# MAX96724_PINOUT.net
KiCad netlist of a schematic drawn in Altium Designer
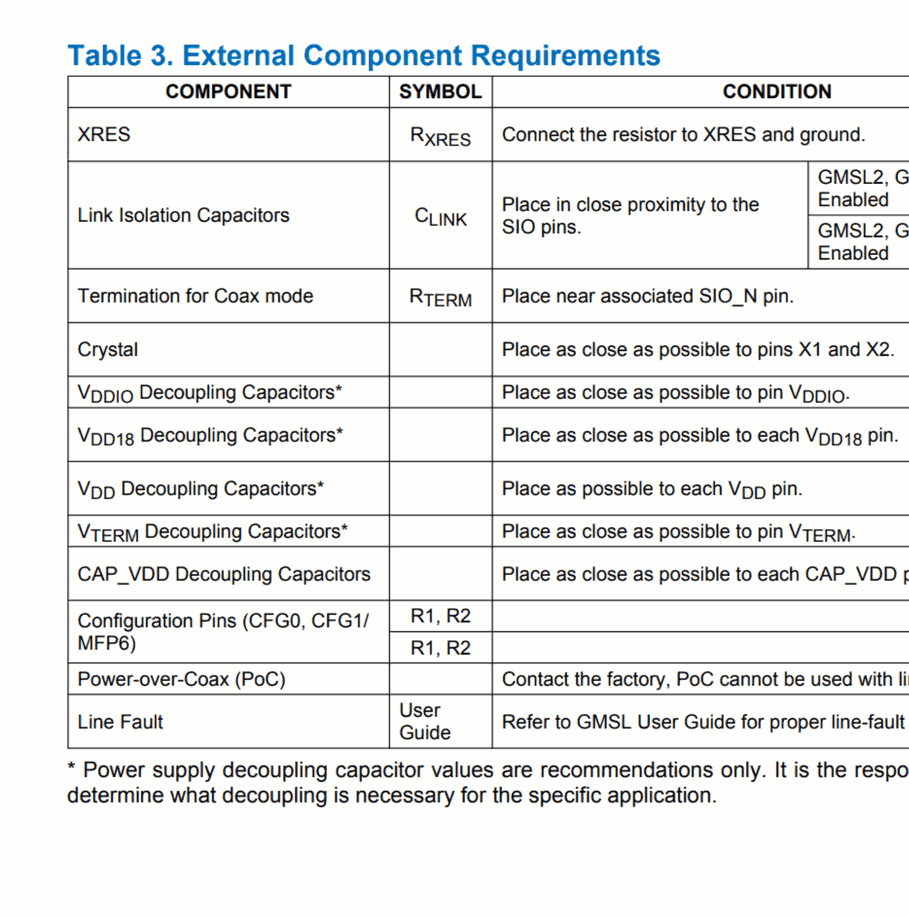
[diagram p0: MAX96724_PINOUT.SchDoc, top left]
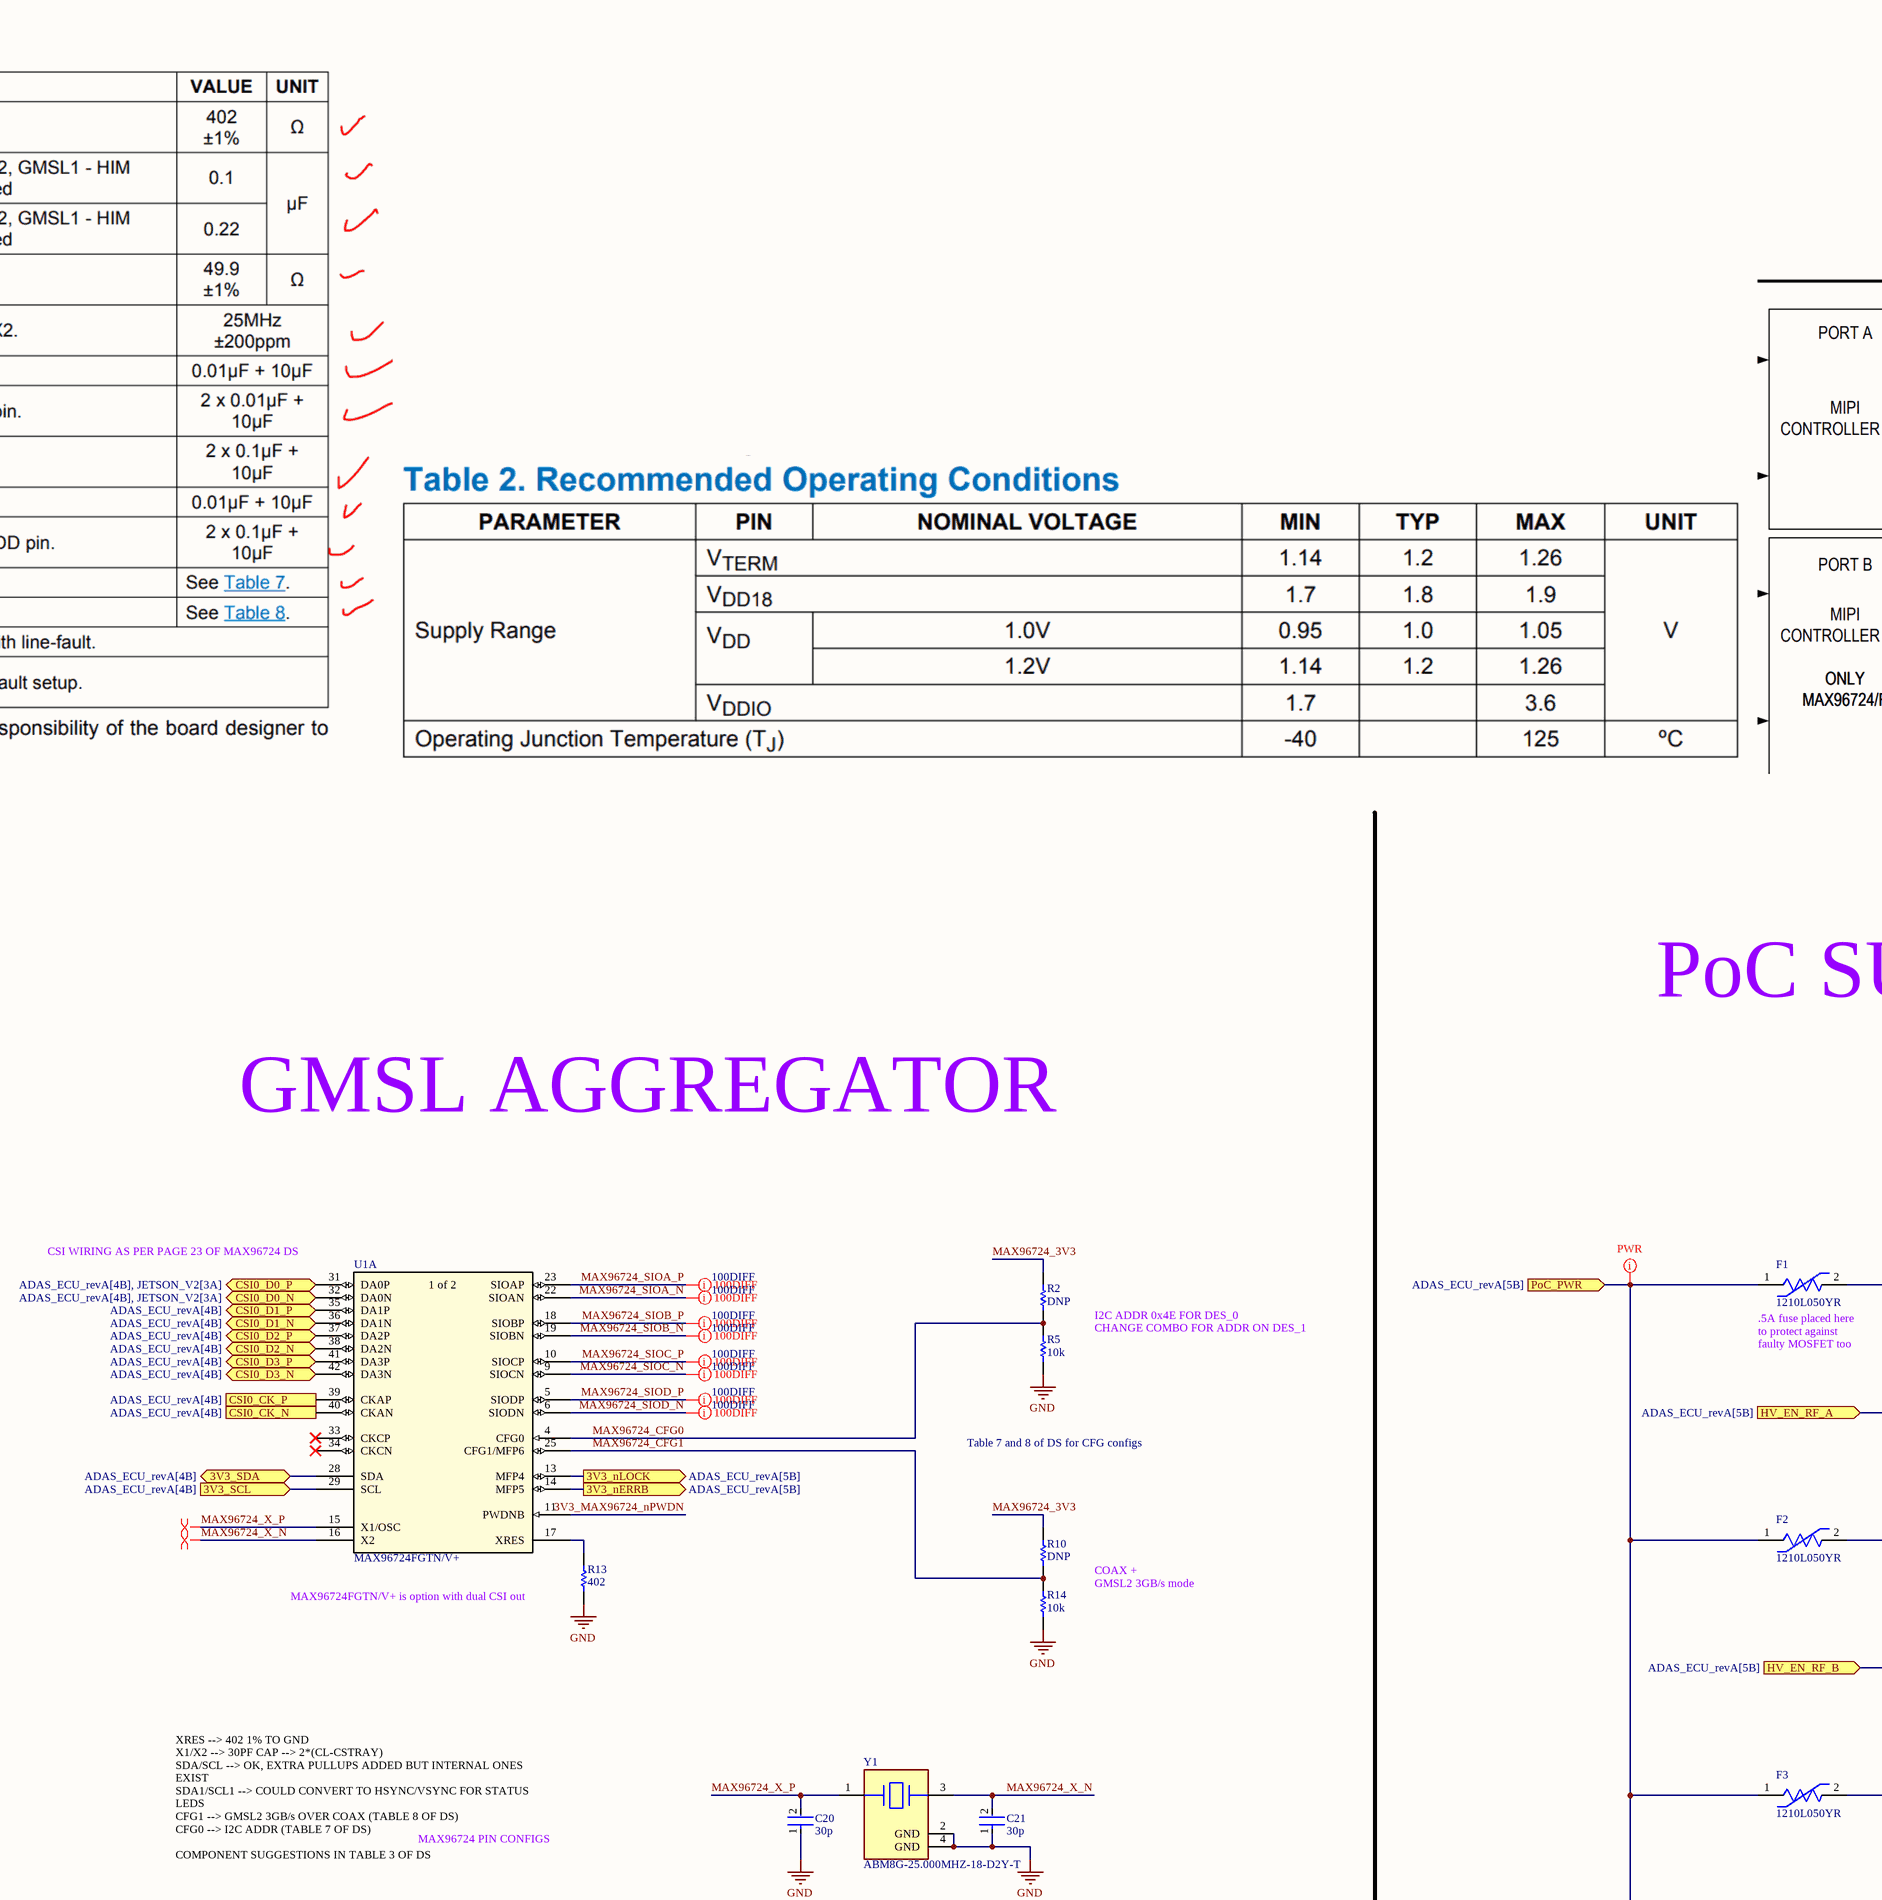
[diagram p1: MAX96724_PINOUT.SchDoc, top middle]
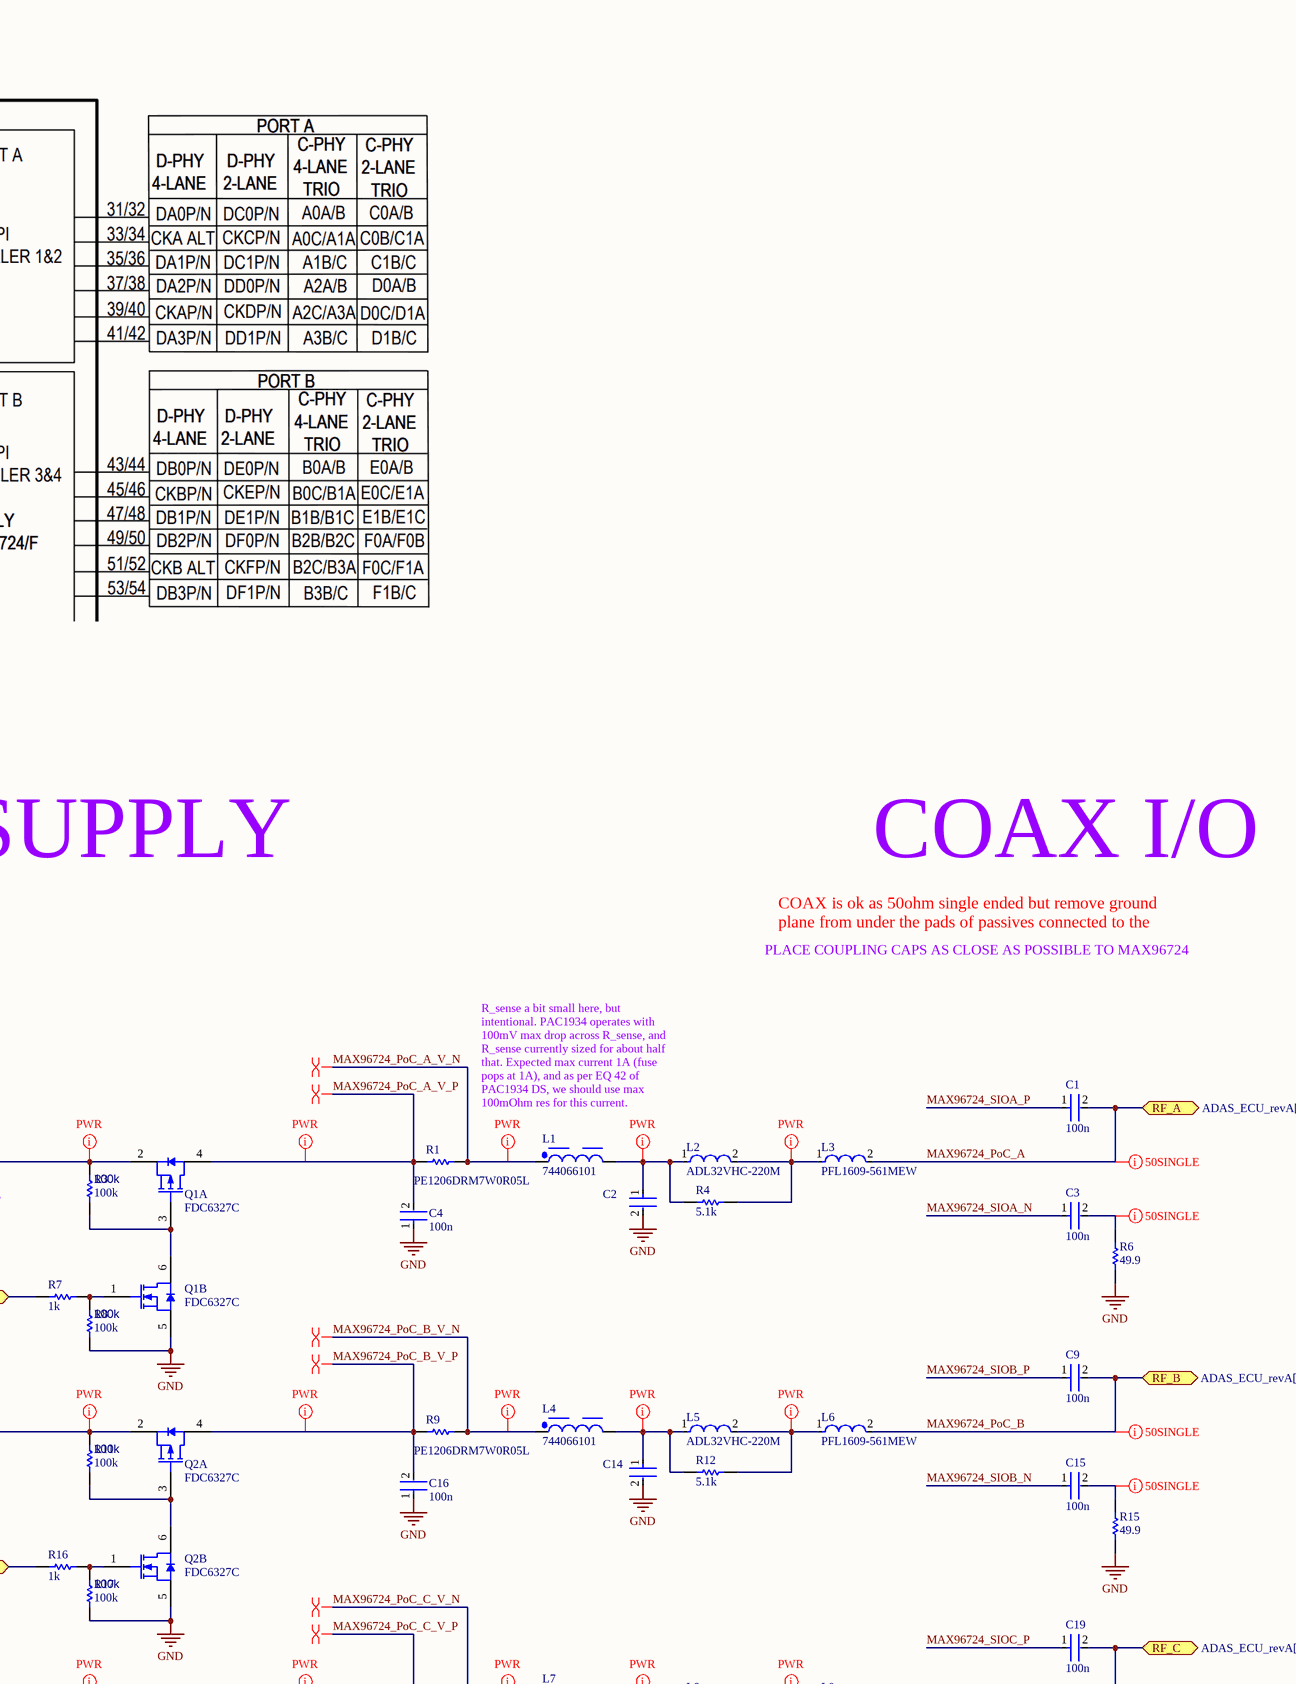
[diagram p2: MAX96724_PINOUT.SchDoc, top right]
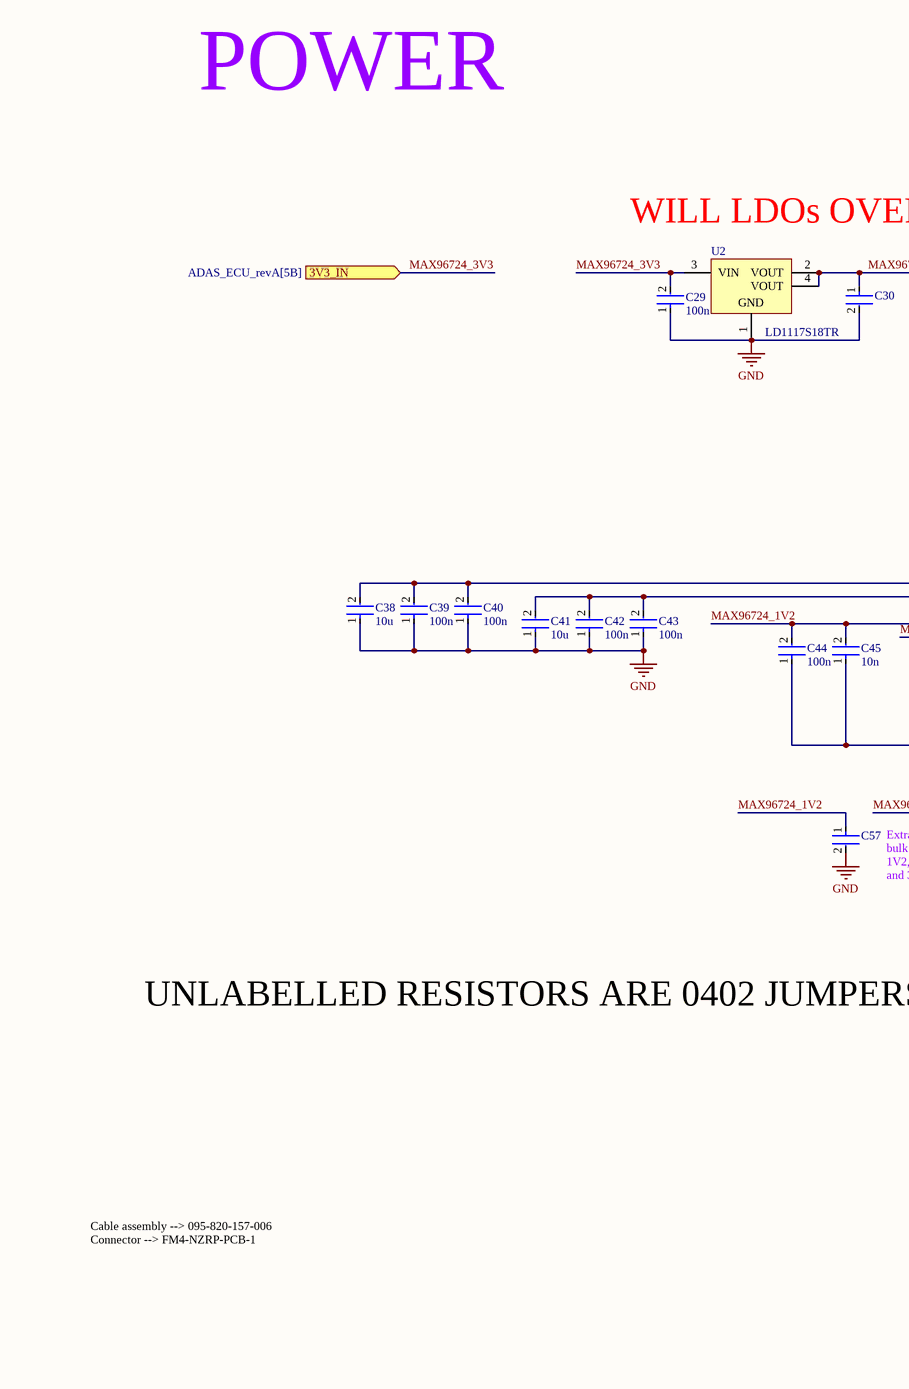
[diagram p3: MAX96724_PINOUT.SchDoc, bottom left]
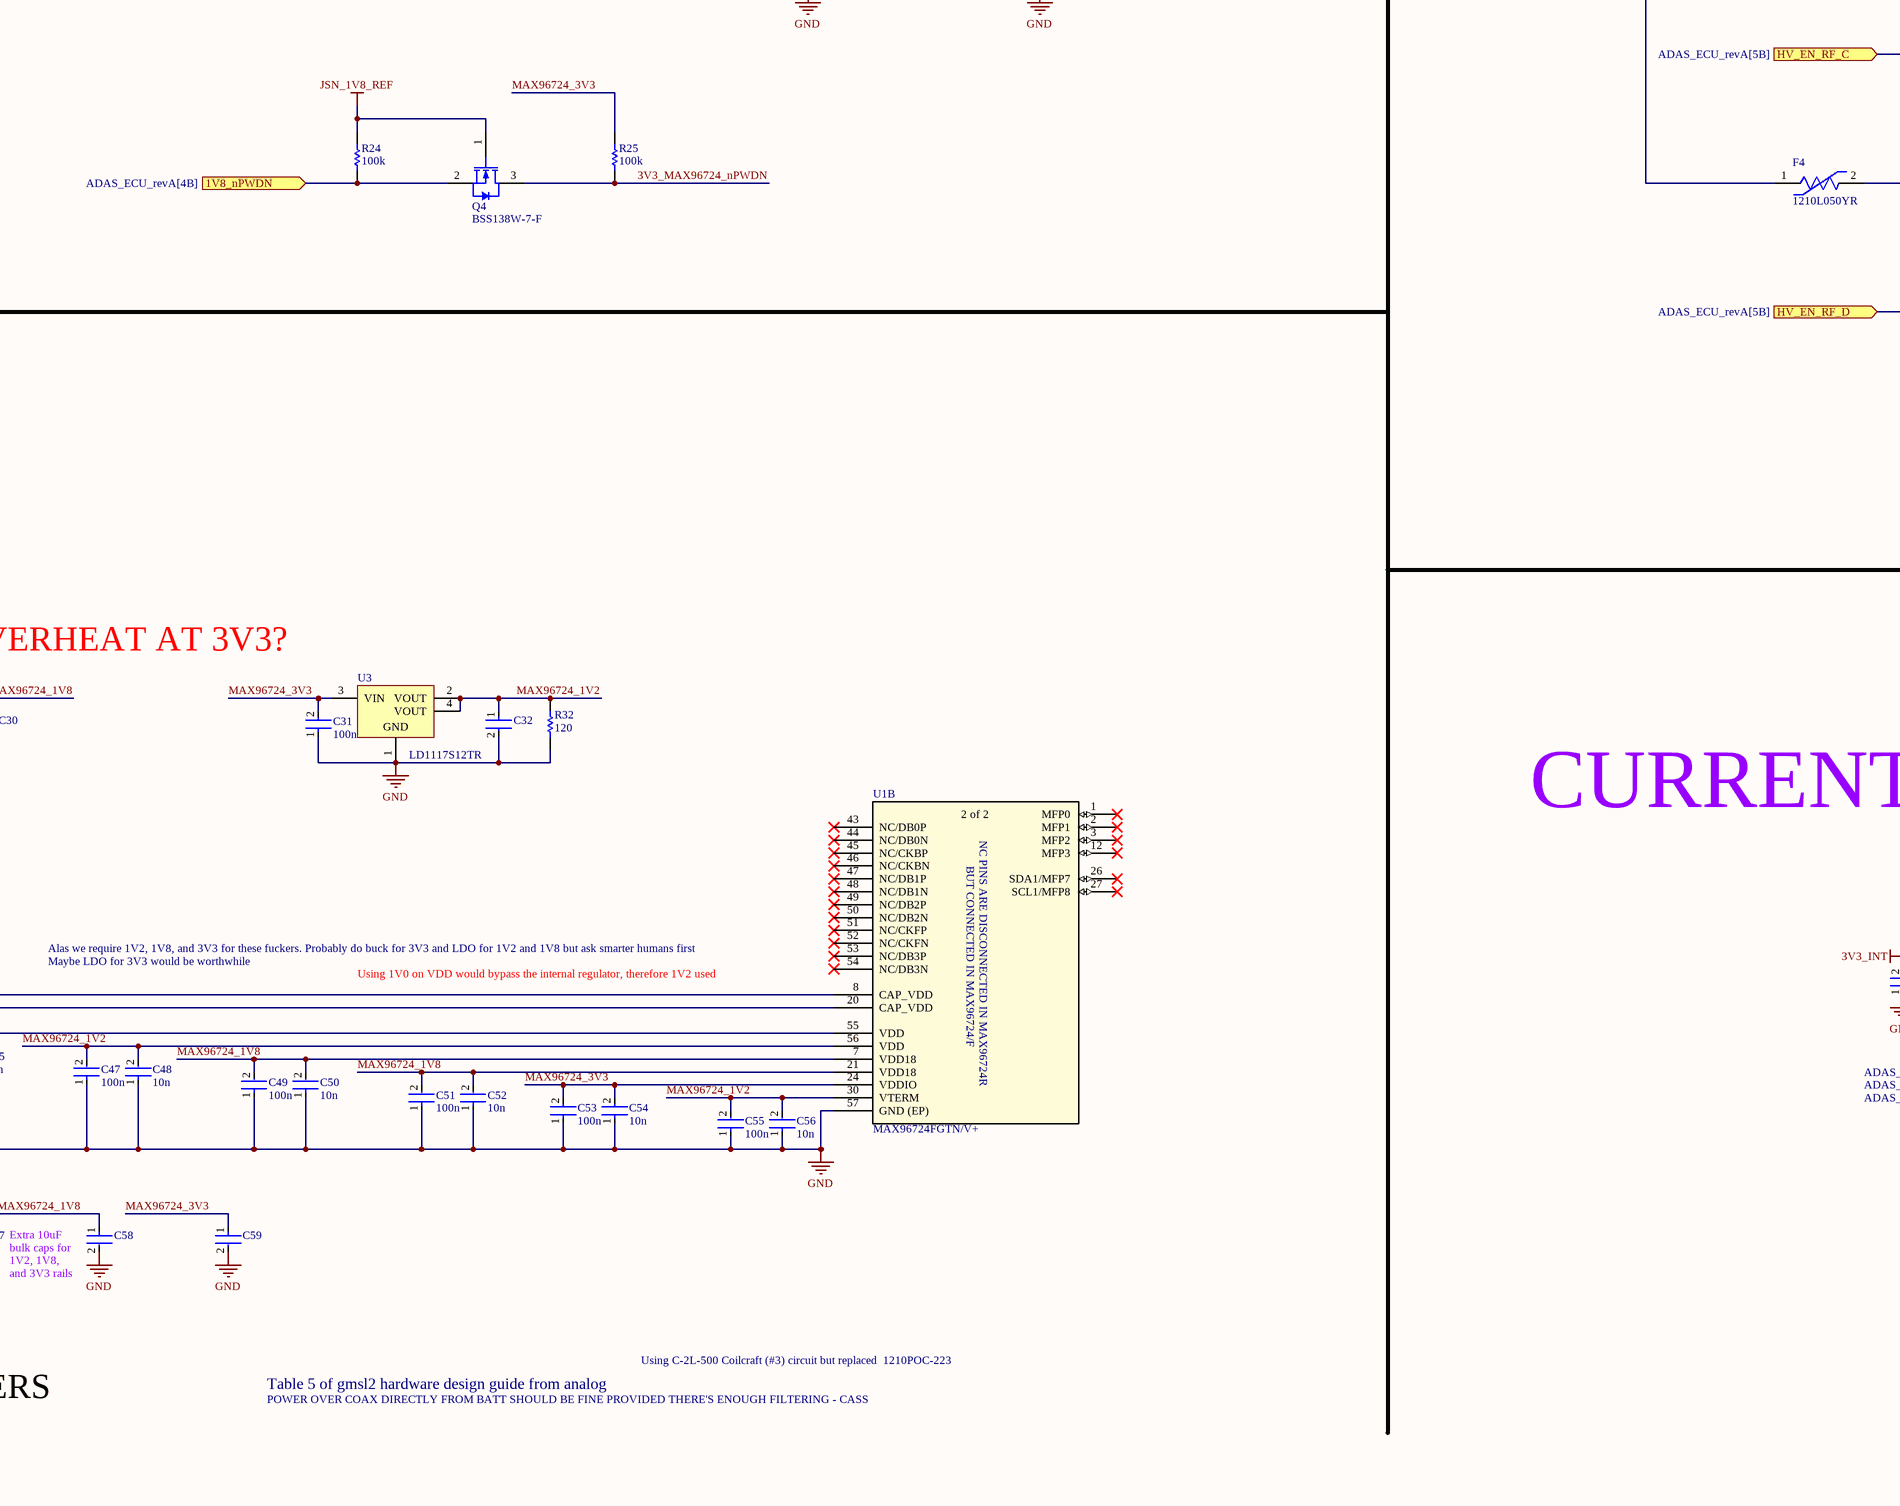
[diagram p4: MAX96724_PINOUT.SchDoc, bottom middle]
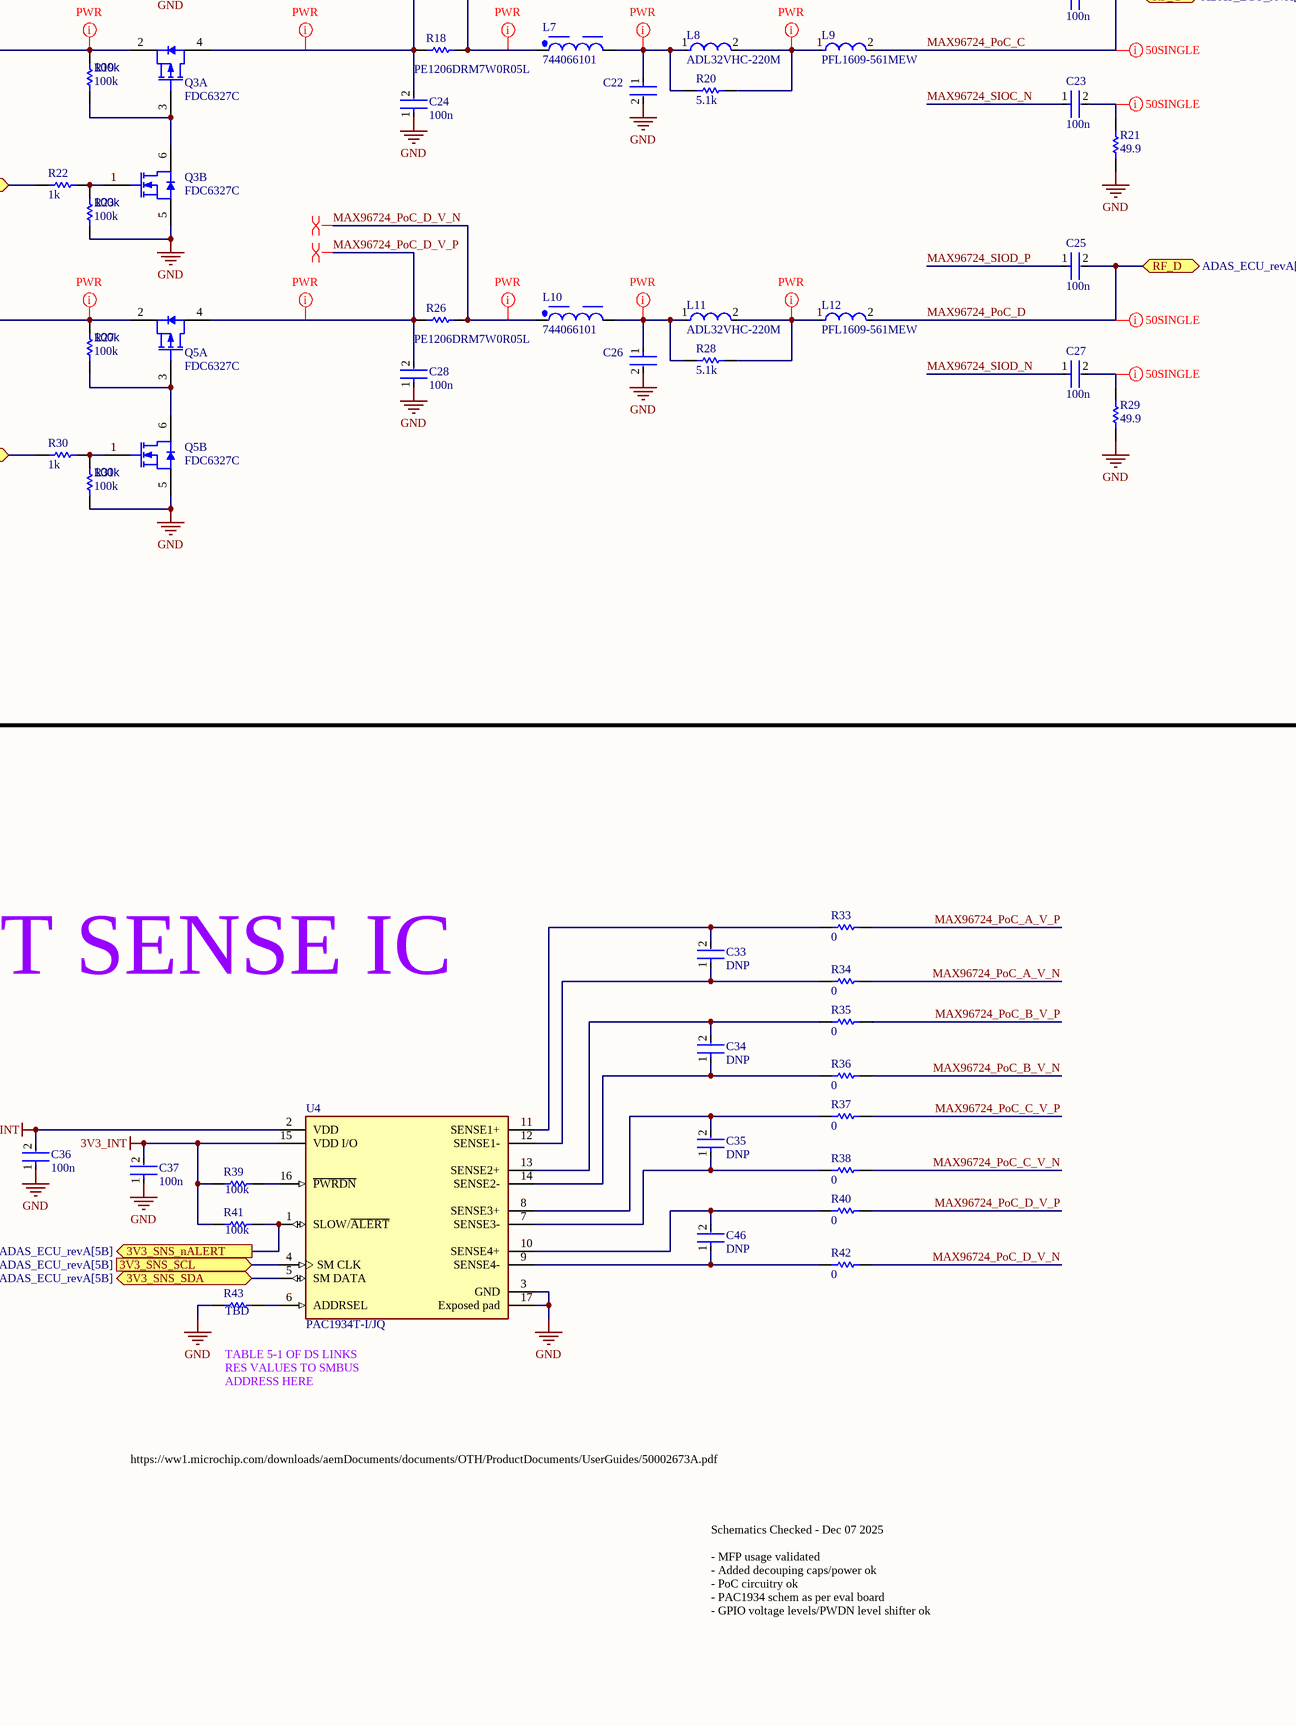
[diagram p5: MAX96724_PINOUT.SchDoc, bottom right]

(export (version "E")
  (design (tool "Eeschema 10.0.6"))
  (components
    (comp (ref "C1")
      (value "100n")
      (footprint "FP-0402-L_1_0_0_05-W_0_5-IPC_A")
      (description "LARGE PADS, 0402 CAP, CHANGE COMMENT TO MATCH REAL P/N")
      (libsource (lib "Space Concordia") (part "b4654b650e69147ec39a6b967a45e02"))
    )
    (comp (ref "C2")
      (value "GRM21BR61E226ME44L")
      (footprint "FP-GRM21B-0_2-e0_2_0_7-IPC_B")
      (description "Chip Multilayer Ceramic Capacitors for General Purpose, 0805, 22uF, X5R, 15%, 20%, 25V")
      (fields (field (name "TOLERANCE") "20%") (field (name "VOLTAGE") "25V"))
      (libsource (lib "Altium Content Vault") (part "b4654b650e69147ec39a6b967a45e02"))
    )
    (comp (ref "C3")
      (value "100n")
      (footprint "FP-0402-L_1_0_0_05-W_0_5-IPC_A")
      (description "LARGE PADS, 0402 CAP, CHANGE COMMENT TO MATCH REAL P/N")
      (libsource (lib "Space Concordia") (part "b4654b650e69147ec39a6b967a45e02"))
    )
    (comp (ref "C4")
      (value "100n")
      (footprint "FP-0402-L_1_0_0_05-W_0_5-IPC_A")
      (description "LARGE PADS, 0402 CAP, CHANGE COMMENT TO MATCH REAL P/N")
      (libsource (lib "Space Concordia") (part "b4654b650e69147ec39a6b967a45e02"))
    )
    (comp (ref "C9")
      (value "100n")
      (footprint "FP-0402-L_1_0_0_05-W_0_5-IPC_A")
      (description "LARGE PADS, 0402 CAP, CHANGE COMMENT TO MATCH REAL P/N")
      (libsource (lib "Space Concordia") (part "b4654b650e69147ec39a6b967a45e02"))
    )
    (comp (ref "C14")
      (value "GRM21BR61E226ME44L")
      (footprint "FP-GRM21B-0_2-e0_2_0_7-IPC_B")
      (description "Chip Multilayer Ceramic Capacitors for General Purpose, 0805, 22uF, X5R, 15%, 20%, 25V")
      (fields (field (name "TOLERANCE") "20%") (field (name "VOLTAGE") "25V"))
      (libsource (lib "Altium Content Vault") (part "b4654b650e69147ec39a6b967a45e02"))
    )
    (comp (ref "C15")
      (value "100n")
      (footprint "FP-0402-L_1_0_0_05-W_0_5-IPC_A")
      (description "LARGE PADS, 0402 CAP, CHANGE COMMENT TO MATCH REAL P/N")
      (libsource (lib "Space Concordia") (part "b4654b650e69147ec39a6b967a45e02"))
    )
    (comp (ref "C16")
      (value "100n")
      (footprint "FP-0402-L_1_0_0_05-W_0_5-IPC_A")
      (description "LARGE PADS, 0402 CAP, CHANGE COMMENT TO MATCH REAL P/N")
      (libsource (lib "Space Concordia") (part "b4654b650e69147ec39a6b967a45e02"))
    )
    (comp (ref "C19")
      (value "100n")
      (footprint "FP-0402-L_1_0_0_05-W_0_5-IPC_A")
      (description "LARGE PADS, 0402 CAP, CHANGE COMMENT TO MATCH REAL P/N")
      (libsource (lib "Space Concordia") (part "b4654b650e69147ec39a6b967a45e02"))
    )
    (comp (ref "C20")
      (value "30p")
      (footprint "FP-0402-L_1_0_0_05-W_0_5-IPC_A")
      (description "LARGE PADS, 0402 CAP, CHANGE COMMENT TO MATCH REAL P/N")
      (libsource (lib "Space Concordia") (part "b4654b650e69147ec39a6b967a45e02"))
    )
    (comp (ref "C21")
      (value "30p")
      (footprint "FP-0402-L_1_0_0_05-W_0_5-IPC_A")
      (description "LARGE PADS, 0402 CAP, CHANGE COMMENT TO MATCH REAL P/N")
      (libsource (lib "Space Concordia") (part "b4654b650e69147ec39a6b967a45e02"))
    )
    (comp (ref "C22")
      (value "GRM21BR61E226ME44L")
      (footprint "FP-GRM21B-0_2-e0_2_0_7-IPC_B")
      (description "Chip Multilayer Ceramic Capacitors for General Purpose, 0805, 22uF, X5R, 15%, 20%, 25V")
      (fields (field (name "TOLERANCE") "20%") (field (name "VOLTAGE") "25V"))
      (libsource (lib "Altium Content Vault") (part "b4654b650e69147ec39a6b967a45e02"))
    )
    (comp (ref "C23")
      (value "100n")
      (footprint "FP-0402-L_1_0_0_05-W_0_5-IPC_A")
      (description "LARGE PADS, 0402 CAP, CHANGE COMMENT TO MATCH REAL P/N")
      (libsource (lib "Space Concordia") (part "b4654b650e69147ec39a6b967a45e02"))
    )
    (comp (ref "C24")
      (value "100n")
      (footprint "FP-0402-L_1_0_0_05-W_0_5-IPC_A")
      (description "LARGE PADS, 0402 CAP, CHANGE COMMENT TO MATCH REAL P/N")
      (libsource (lib "Space Concordia") (part "b4654b650e69147ec39a6b967a45e02"))
    )
    (comp (ref "C25")
      (value "100n")
      (footprint "FP-0402-L_1_0_0_05-W_0_5-IPC_A")
      (description "LARGE PADS, 0402 CAP, CHANGE COMMENT TO MATCH REAL P/N")
      (libsource (lib "Space Concordia") (part "b4654b650e69147ec39a6b967a45e02"))
    )
    (comp (ref "C26")
      (value "GRM21BR61E226ME44L")
      (footprint "FP-GRM21B-0_2-e0_2_0_7-IPC_B")
      (description "Chip Multilayer Ceramic Capacitors for General Purpose, 0805, 22uF, X5R, 15%, 20%, 25V")
      (fields (field (name "TOLERANCE") "20%") (field (name "VOLTAGE") "25V"))
      (libsource (lib "Altium Content Vault") (part "b4654b650e69147ec39a6b967a45e02"))
    )
    (comp (ref "C27")
      (value "100n")
      (footprint "FP-0402-L_1_0_0_05-W_0_5-IPC_A")
      (description "LARGE PADS, 0402 CAP, CHANGE COMMENT TO MATCH REAL P/N")
      (libsource (lib "Space Concordia") (part "b4654b650e69147ec39a6b967a45e02"))
    )
    (comp (ref "C28")
      (value "100n")
      (footprint "FP-0402-L_1_0_0_05-W_0_5-IPC_A")
      (description "LARGE PADS, 0402 CAP, CHANGE COMMENT TO MATCH REAL P/N")
      (libsource (lib "Space Concordia") (part "b4654b650e69147ec39a6b967a45e02"))
    )
    (comp (ref "C29")
      (value "100n")
      (footprint "FP-0402-L_1_0_0_05-W_0_5-IPC_A")
      (description "LARGE PADS, 0402 CAP, CHANGE COMMENT TO MATCH REAL P/N")
      (libsource (lib "Space Concordia") (part "b4654b650e69147ec39a6b967a45e02"))
    )
    (comp (ref "C30")
      (value "GRM188R60J106ME47D")
      (footprint "FP-GRM188-0_1-e0_2_0_55-IPC_A")
      (description "Chip Multilayer Ceramic Capacitors for General Purpose, 0603, 10uF, X5R, 15%, 20%, 6.3V")
      (fields (field (name "VOLTAGE") "6.3V") (field (name "TOLERANCE") "20%"))
      (libsource (lib "Altium Content Vault") (part "02cd4be3c70576c341d710602a673aa"))
    )
    (comp (ref "C31")
      (value "100n")
      (footprint "FP-0402-L_1_0_0_05-W_0_5-IPC_A")
      (description "LARGE PADS, 0402 CAP, CHANGE COMMENT TO MATCH REAL P/N")
      (libsource (lib "Space Concordia") (part "b4654b650e69147ec39a6b967a45e02"))
    )
    (comp (ref "C32")
      (value "GRM188R60J106ME47D")
      (footprint "FP-GRM188-0_1-e0_2_0_55-IPC_A")
      (description "Chip Multilayer Ceramic Capacitors for General Purpose, 0603, 10uF, X5R, 15%, 20%, 6.3V")
      (fields (field (name "VOLTAGE") "6.3V") (field (name "TOLERANCE") "20%"))
      (libsource (lib "Altium Content Vault") (part "02cd4be3c70576c341d710602a673aa"))
    )
    (comp (ref "C33")
      (value "DNP")
      (footprint "FP-0402-L_1_0_0_05-W_0_5-IPC_A")
      (description "LARGE PADS, 0402 CAP, CHANGE COMMENT TO MATCH REAL P/N")
      (libsource (lib "Space Concordia") (part "b4654b650e69147ec39a6b967a45e02"))
    )
    (comp (ref "C34")
      (value "DNP")
      (footprint "FP-0402-L_1_0_0_05-W_0_5-IPC_A")
      (description "LARGE PADS, 0402 CAP, CHANGE COMMENT TO MATCH REAL P/N")
      (libsource (lib "Space Concordia") (part "b4654b650e69147ec39a6b967a45e02"))
    )
    (comp (ref "C35")
      (value "DNP")
      (footprint "FP-0402-L_1_0_0_05-W_0_5-IPC_A")
      (description "LARGE PADS, 0402 CAP, CHANGE COMMENT TO MATCH REAL P/N")
      (libsource (lib "Space Concordia") (part "b4654b650e69147ec39a6b967a45e02"))
    )
    (comp (ref "C36")
      (value "100n")
      (footprint "FP-0402-L_1_0_0_05-W_0_5-IPC_A")
      (description "LARGE PADS, 0402 CAP, CHANGE COMMENT TO MATCH REAL P/N")
      (libsource (lib "Space Concordia") (part "b4654b650e69147ec39a6b967a45e02"))
    )
    (comp (ref "C37")
      (value "100n")
      (footprint "FP-0402-L_1_0_0_05-W_0_5-IPC_A")
      (description "LARGE PADS, 0402 CAP, CHANGE COMMENT TO MATCH REAL P/N")
      (libsource (lib "Space Concordia") (part "b4654b650e69147ec39a6b967a45e02"))
    )
    (comp (ref "C38")
      (value "10u")
      (footprint "FP-0402-L_1_0_0_05-W_0_5-IPC_A")
      (description "LARGE PADS, 0402 CAP, CHANGE COMMENT TO MATCH REAL P/N")
      (libsource (lib "Space Concordia") (part "b4654b650e69147ec39a6b967a45e02"))
    )
    (comp (ref "C39")
      (value "100n")
      (footprint "FP-0402-L_1_0_0_05-W_0_5-IPC_A")
      (description "LARGE PADS, 0402 CAP, CHANGE COMMENT TO MATCH REAL P/N")
      (libsource (lib "Space Concordia") (part "b4654b650e69147ec39a6b967a45e02"))
    )
    (comp (ref "C40")
      (value "100n")
      (footprint "FP-0402-L_1_0_0_05-W_0_5-IPC_A")
      (description "LARGE PADS, 0402 CAP, CHANGE COMMENT TO MATCH REAL P/N")
      (libsource (lib "Space Concordia") (part "b4654b650e69147ec39a6b967a45e02"))
    )
    (comp (ref "C41")
      (value "10u")
      (footprint "FP-0402-L_1_0_0_05-W_0_5-IPC_A")
      (description "LARGE PADS, 0402 CAP, CHANGE COMMENT TO MATCH REAL P/N")
      (libsource (lib "Space Concordia") (part "b4654b650e69147ec39a6b967a45e02"))
    )
    (comp (ref "C42")
      (value "100n")
      (footprint "FP-0402-L_1_0_0_05-W_0_5-IPC_A")
      (description "LARGE PADS, 0402 CAP, CHANGE COMMENT TO MATCH REAL P/N")
      (libsource (lib "Space Concordia") (part "b4654b650e69147ec39a6b967a45e02"))
    )
    (comp (ref "C43")
      (value "100n")
      (footprint "FP-0402-L_1_0_0_05-W_0_5-IPC_A")
      (description "LARGE PADS, 0402 CAP, CHANGE COMMENT TO MATCH REAL P/N")
      (libsource (lib "Space Concordia") (part "b4654b650e69147ec39a6b967a45e02"))
    )
    (comp (ref "C44")
      (value "100n")
      (footprint "FP-0402-L_1_0_0_05-W_0_5-IPC_A")
      (description "LARGE PADS, 0402 CAP, CHANGE COMMENT TO MATCH REAL P/N")
      (libsource (lib "Space Concordia") (part "b4654b650e69147ec39a6b967a45e02"))
    )
    (comp (ref "C45")
      (value "10n")
      (footprint "FP-0402-L_1_0_0_05-W_0_5-IPC_A")
      (description "LARGE PADS, 0402 CAP, CHANGE COMMENT TO MATCH REAL P/N")
      (libsource (lib "Space Concordia") (part "b4654b650e69147ec39a6b967a45e02"))
    )
    (comp (ref "C46")
      (value "DNP")
      (footprint "FP-0402-L_1_0_0_05-W_0_5-IPC_A")
      (description "LARGE PADS, 0402 CAP, CHANGE COMMENT TO MATCH REAL P/N")
      (libsource (lib "Space Concordia") (part "b4654b650e69147ec39a6b967a45e02"))
    )
    (comp (ref "C47")
      (value "100n")
      (footprint "FP-0402-L_1_0_0_05-W_0_5-IPC_A")
      (description "LARGE PADS, 0402 CAP, CHANGE COMMENT TO MATCH REAL P/N")
      (libsource (lib "Space Concordia") (part "b4654b650e69147ec39a6b967a45e02"))
    )
    (comp (ref "C48")
      (value "10n")
      (footprint "FP-0402-L_1_0_0_05-W_0_5-IPC_A")
      (description "LARGE PADS, 0402 CAP, CHANGE COMMENT TO MATCH REAL P/N")
      (libsource (lib "Space Concordia") (part "b4654b650e69147ec39a6b967a45e02"))
    )
    (comp (ref "C49")
      (value "100n")
      (footprint "FP-0402-L_1_0_0_05-W_0_5-IPC_A")
      (description "LARGE PADS, 0402 CAP, CHANGE COMMENT TO MATCH REAL P/N")
      (libsource (lib "Space Concordia") (part "b4654b650e69147ec39a6b967a45e02"))
    )
    (comp (ref "C50")
      (value "10n")
      (footprint "FP-0402-L_1_0_0_05-W_0_5-IPC_A")
      (description "LARGE PADS, 0402 CAP, CHANGE COMMENT TO MATCH REAL P/N")
      (libsource (lib "Space Concordia") (part "b4654b650e69147ec39a6b967a45e02"))
    )
    (comp (ref "C51")
      (value "100n")
      (footprint "FP-0402-L_1_0_0_05-W_0_5-IPC_A")
      (description "LARGE PADS, 0402 CAP, CHANGE COMMENT TO MATCH REAL P/N")
      (libsource (lib "Space Concordia") (part "b4654b650e69147ec39a6b967a45e02"))
    )
    (comp (ref "C52")
      (value "10n")
      (footprint "FP-0402-L_1_0_0_05-W_0_5-IPC_A")
      (description "LARGE PADS, 0402 CAP, CHANGE COMMENT TO MATCH REAL P/N")
      (libsource (lib "Space Concordia") (part "b4654b650e69147ec39a6b967a45e02"))
    )
    (comp (ref "C53")
      (value "100n")
      (footprint "FP-0402-L_1_0_0_05-W_0_5-IPC_A")
      (description "LARGE PADS, 0402 CAP, CHANGE COMMENT TO MATCH REAL P/N")
      (libsource (lib "Space Concordia") (part "b4654b650e69147ec39a6b967a45e02"))
    )
    (comp (ref "C54")
      (value "10n")
      (footprint "FP-0402-L_1_0_0_05-W_0_5-IPC_A")
      (description "LARGE PADS, 0402 CAP, CHANGE COMMENT TO MATCH REAL P/N")
      (libsource (lib "Space Concordia") (part "b4654b650e69147ec39a6b967a45e02"))
    )
    (comp (ref "C55")
      (value "100n")
      (footprint "FP-0402-L_1_0_0_05-W_0_5-IPC_A")
      (description "LARGE PADS, 0402 CAP, CHANGE COMMENT TO MATCH REAL P/N")
      (libsource (lib "Space Concordia") (part "b4654b650e69147ec39a6b967a45e02"))
    )
    (comp (ref "C56")
      (value "10n")
      (footprint "FP-0402-L_1_0_0_05-W_0_5-IPC_A")
      (description "LARGE PADS, 0402 CAP, CHANGE COMMENT TO MATCH REAL P/N")
      (libsource (lib "Space Concordia") (part "b4654b650e69147ec39a6b967a45e02"))
    )
    (comp (ref "C57")
      (value "EMK107BBJ106MA-T")
      (footprint "FP-0603-L_1_6_0_2-W_0_8_0-MFG")
      (description "Multilayer Ceramic Capacitor 10uF 16V X5R 20% SMD 0603 T/R")
      (fields (field (name "TOLERANCE") "20%"))
      (libsource (lib "Altium Content Vault") (part "b4654b650e69147ec39a6b967a45e02"))
    )
    (comp (ref "C58")
      (value "EMK107BBJ106MA-T")
      (footprint "FP-0603-L_1_6_0_2-W_0_8_0-MFG")
      (description "Multilayer Ceramic Capacitor 10uF 16V X5R 20% SMD 0603 T/R")
      (fields (field (name "TOLERANCE") "20%"))
      (libsource (lib "Altium Content Vault") (part "b4654b650e69147ec39a6b967a45e02"))
    )
    (comp (ref "C59")
      (value "EMK107BBJ106MA-T")
      (footprint "FP-0603-L_1_6_0_2-W_0_8_0-MFG")
      (description "Multilayer Ceramic Capacitor 10uF 16V X5R 20% SMD 0603 T/R")
      (fields (field (name "TOLERANCE") "20%"))
      (libsource (lib "Altium Content Vault") (part "b4654b650e69147ec39a6b967a45e02"))
    )
    (comp (ref "F1")
      (value "1210L050YR")
      (footprint "FP-1210L050YR-MFG")
      (description "PTC RESET FUSE 13.2V 500MA 1210")
      (libsource (lib "Altium Content Vault") (part "fc31388045fc42ab786d6d00b506e9f"))
    )
    (comp (ref "F2")
      (value "1210L050YR")
      (footprint "FP-1210L050YR-MFG")
      (description "PTC RESET FUSE 13.2V 500MA 1210")
      (libsource (lib "Altium Content Vault") (part "fc31388045fc42ab786d6d00b506e9f"))
    )
    (comp (ref "F3")
      (value "1210L050YR")
      (footprint "FP-1210L050YR-MFG")
      (description "PTC RESET FUSE 13.2V 500MA 1210")
      (libsource (lib "Altium Content Vault") (part "fc31388045fc42ab786d6d00b506e9f"))
    )
    (comp (ref "F4")
      (value "1210L050YR")
      (footprint "FP-1210L050YR-MFG")
      (description "PTC RESET FUSE 13.2V 500MA 1210")
      (libsource (lib "Altium Content Vault") (part "fc31388045fc42ab786d6d00b506e9f"))
    )
    (comp (ref "L1")
      (value "744066101")
      (footprint "WE-TPC_1038")
      (fields (field (name "TOLERANCE") "30%"))
      (libsource (lib "Altium Content Vault") (part "Inductor - 2"))
    )
    (comp (ref "L2")
      (value "ADL32VHC-220M")
      (footprint "FP-1210POC-MFG")
      (description "NOT COILCRAFT - ACTUAL P# --> ADL32VHC-220M\r\n - Power Injection Chokes for PoC")
      (fields
        (field (name "MANUFACTURER") "coilcraft")
        (field (name "OCTOPART") "https://octopart.com/1210poc-223mrc-coilcraft-103207315")
      )
      (libsource (lib "Altium Content Vault") (part "725321dda6339637d4d059423bc1c3c"))
    )
    (comp (ref "L3")
      (value "PFL1609-561MEW")
      (footprint "FP-PFL1609-MFG")
      (description "Fixed Inductors PFL1609 Low Profile 0.56 uH 20 % 1.4 A")
      (fields (field (name "MANUFACTURER") "coilcraft") (field (name "TOLERANCE") "20%"))
      (libsource (lib "Altium Content Vault") (part "725321dda6339637d4d059423bc1c3c"))
    )
    (comp (ref "L4")
      (value "744066101")
      (footprint "WE-TPC_1038")
      (fields (field (name "TOLERANCE") "30%"))
      (libsource (lib "Altium Content Vault") (part "Inductor - 2"))
    )
    (comp (ref "L5")
      (value "ADL32VHC-220M")
      (footprint "FP-1210POC-MFG")
      (description "NOT COILCRAFT - ACTUAL P# --> ADL32VHC-220M\r\n - Power Injection Chokes for PoC")
      (fields
        (field (name "MANUFACTURER") "coilcraft")
        (field (name "OCTOPART") "https://octopart.com/1210poc-223mrc-coilcraft-103207315")
      )
      (libsource (lib "Altium Content Vault") (part "725321dda6339637d4d059423bc1c3c"))
    )
    (comp (ref "L6")
      (value "PFL1609-561MEW")
      (footprint "FP-PFL1609-MFG")
      (description "Fixed Inductors PFL1609 Low Profile 0.56 uH 20 % 1.4 A")
      (fields (field (name "MANUFACTURER") "coilcraft") (field (name "TOLERANCE") "20%"))
      (libsource (lib "Altium Content Vault") (part "725321dda6339637d4d059423bc1c3c"))
    )
    (comp (ref "L7")
      (value "744066101")
      (footprint "WE-TPC_1038")
      (fields (field (name "TOLERANCE") "30%"))
      (libsource (lib "Altium Content Vault") (part "Inductor - 2"))
    )
    (comp (ref "L8")
      (value "ADL32VHC-220M")
      (footprint "FP-1210POC-MFG")
      (description "NOT COILCRAFT - ACTUAL P# --> ADL32VHC-220M\r\n - Power Injection Chokes for PoC")
      (fields
        (field (name "MANUFACTURER") "coilcraft")
        (field (name "OCTOPART") "https://octopart.com/1210poc-223mrc-coilcraft-103207315")
      )
      (libsource (lib "Altium Content Vault") (part "725321dda6339637d4d059423bc1c3c"))
    )
    (comp (ref "L9")
      (value "PFL1609-561MEW")
      (footprint "FP-PFL1609-MFG")
      (description "Fixed Inductors PFL1609 Low Profile 0.56 uH 20 % 1.4 A")
      (fields (field (name "MANUFACTURER") "coilcraft") (field (name "TOLERANCE") "20%"))
      (libsource (lib "Altium Content Vault") (part "725321dda6339637d4d059423bc1c3c"))
    )
    (comp (ref "L10")
      (value "744066101")
      (footprint "WE-TPC_1038")
      (fields (field (name "TOLERANCE") "30%"))
      (libsource (lib "Altium Content Vault") (part "Inductor - 2"))
    )
    (comp (ref "L11")
      (value "ADL32VHC-220M")
      (footprint "FP-1210POC-MFG")
      (description "NOT COILCRAFT - ACTUAL P# --> ADL32VHC-220M\r\n - Power Injection Chokes for PoC")
      (fields
        (field (name "MANUFACTURER") "coilcraft")
        (field (name "OCTOPART") "https://octopart.com/1210poc-223mrc-coilcraft-103207315")
      )
      (libsource (lib "Altium Content Vault") (part "725321dda6339637d4d059423bc1c3c"))
    )
    (comp (ref "L12")
      (value "PFL1609-561MEW")
      (footprint "FP-PFL1609-MFG")
      (description "Fixed Inductors PFL1609 Low Profile 0.56 uH 20 % 1.4 A")
      (fields (field (name "MANUFACTURER") "coilcraft") (field (name "TOLERANCE") "20%"))
      (libsource (lib "Altium Content Vault") (part "725321dda6339637d4d059423bc1c3c"))
    )
    (comp (ref "Q1")
      (value "FDC6327C")
      (footprint "FAIR-SOT23-6_V")
      (fields (field (name "MANUFACTURER") "Fairchild"))
      (libsource (lib "Altium Content Vault") (part "PEMOS-SGD-NEMOS-GSD-6"))
    )
    (comp (ref "Q2")
      (value "FDC6327C")
      (footprint "FAIR-SOT23-6_V")
      (fields (field (name "MANUFACTURER") "Fairchild"))
      (libsource (lib "Altium Content Vault") (part "PEMOS-SGD-NEMOS-GSD-6"))
    )
    (comp (ref "Q3")
      (value "FDC6327C")
      (footprint "FAIR-SOT23-6_V")
      (fields (field (name "MANUFACTURER") "Fairchild"))
      (libsource (lib "Altium Content Vault") (part "PEMOS-SGD-NEMOS-GSD-6"))
    )
    (comp (ref "Q4")
      (value "BSS138W-7-F")
      (footprint "DIOD-SOT323-3_V")
      (fields (field (name "MANUFACTURER") "DiodesIncorporated"))
      (libsource (lib "Altium Content Vault") (part "NEMOS-GSD-3"))
    )
    (comp (ref "Q5")
      (value "FDC6327C")
      (footprint "FAIR-SOT23-6_V")
      (fields (field (name "MANUFACTURER") "Fairchild"))
      (libsource (lib "Altium Content Vault") (part "PEMOS-SGD-NEMOS-GSD-6"))
    )
    (comp (ref "R1")
      (value "PE1206DRM7W0R05L")
      (footprint "R1206B")
      (libsource (lib "Space Concordia") (part "Resistor"))
    )
    (comp (ref "R2")
      (value "DNP")
      (footprint "R0603B")
      (description "Resistor")
      (libsource (lib "Space Concordia") (part "Resistor"))
    )
    (comp (ref "R3")
      (value "100k")
      (footprint "R0603B")
      (description "Resistor")
      (fields (field (name "ALTIUM_VALUE") "100k"))
      (libsource (lib "Space Concordia") (part "Resistor"))
    )
    (comp (ref "R4")
      (value "5.1k")
      (footprint "R0603B")
      (description "Resistor")
      (libsource (lib "Space Concordia") (part "Resistor"))
    )
    (comp (ref "R5")
      (value "10k")
      (footprint "R0603B")
      (description "Resistor")
      (libsource (lib "Space Concordia") (part "Resistor"))
    )
    (comp (ref "R6")
      (value "49.9")
      (footprint "R0603B")
      (description "Resistor")
      (libsource (lib "Space Concordia") (part "Resistor"))
    )
    (comp (ref "R7")
      (value "1k")
      (footprint "R0603B")
      (description "Resistor")
      (libsource (lib "Space Concordia") (part "Resistor"))
    )
    (comp (ref "R8")
      (value "100k")
      (footprint "R0603B")
      (description "Resistor")
      (fields (field (name "ALTIUM_VALUE") "100k"))
      (libsource (lib "Space Concordia") (part "Resistor"))
    )
    (comp (ref "R9")
      (value "PE1206DRM7W0R05L")
      (footprint "R1206B")
      (libsource (lib "Space Concordia") (part "Resistor"))
    )
    (comp (ref "R10")
      (value "DNP")
      (footprint "R0603B")
      (description "Resistor")
      (libsource (lib "Space Concordia") (part "Resistor"))
    )
    (comp (ref "R11")
      (value "100k")
      (footprint "R0603B")
      (description "Resistor")
      (fields (field (name "ALTIUM_VALUE") "100k"))
      (libsource (lib "Space Concordia") (part "Resistor"))
    )
    (comp (ref "R12")
      (value "5.1k")
      (footprint "R0603B")
      (description "Resistor")
      (libsource (lib "Space Concordia") (part "Resistor"))
    )
    (comp (ref "R13")
      (value "402")
      (footprint "R0603B")
      (description "Resistor")
      (libsource (lib "Space Concordia") (part "Resistor"))
    )
    (comp (ref "R14")
      (value "10k")
      (footprint "R0603B")
      (description "Resistor")
      (libsource (lib "Space Concordia") (part "Resistor"))
    )
    (comp (ref "R15")
      (value "49.9")
      (footprint "R0603B")
      (description "Resistor")
      (libsource (lib "Space Concordia") (part "Resistor"))
    )
    (comp (ref "R16")
      (value "1k")
      (footprint "R0603B")
      (description "Resistor")
      (libsource (lib "Space Concordia") (part "Resistor"))
    )
    (comp (ref "R17")
      (value "100k")
      (footprint "R0603B")
      (description "Resistor")
      (fields (field (name "ALTIUM_VALUE") "100k"))
      (libsource (lib "Space Concordia") (part "Resistor"))
    )
    (comp (ref "R18")
      (value "PE1206DRM7W0R05L")
      (footprint "R1206B")
      (libsource (lib "Space Concordia") (part "Resistor"))
    )
    (comp (ref "R19")
      (value "100k")
      (footprint "R0603B")
      (description "Resistor")
      (fields (field (name "ALTIUM_VALUE") "100k"))
      (libsource (lib "Space Concordia") (part "Resistor"))
    )
    (comp (ref "R20")
      (value "5.1k")
      (footprint "R0603B")
      (description "Resistor")
      (libsource (lib "Space Concordia") (part "Resistor"))
    )
    (comp (ref "R21")
      (value "49.9")
      (footprint "R0603B")
      (description "Resistor")
      (libsource (lib "Space Concordia") (part "Resistor"))
    )
    (comp (ref "R22")
      (value "1k")
      (footprint "R0603B")
      (description "Resistor")
      (libsource (lib "Space Concordia") (part "Resistor"))
    )
    (comp (ref "R23")
      (value "100k")
      (footprint "R0603B")
      (description "Resistor")
      (fields (field (name "ALTIUM_VALUE") "100k"))
      (libsource (lib "Space Concordia") (part "Resistor"))
    )
    (comp (ref "R24")
      (value "100k")
      (footprint "R0603B")
      (description "Resistor")
      (libsource (lib "Space Concordia") (part "Resistor"))
    )
    (comp (ref "R25")
      (value "100k")
      (footprint "R0603B")
      (description "Resistor")
      (libsource (lib "Space Concordia") (part "Resistor"))
    )
    (comp (ref "R26")
      (value "PE1206DRM7W0R05L")
      (footprint "R1206B")
      (libsource (lib "Space Concordia") (part "Resistor"))
    )
    (comp (ref "R27")
      (value "100k")
      (footprint "R0603B")
      (description "Resistor")
      (fields (field (name "ALTIUM_VALUE") "100k"))
      (libsource (lib "Space Concordia") (part "Resistor"))
    )
    (comp (ref "R28")
      (value "5.1k")
      (footprint "R0603B")
      (description "Resistor")
      (libsource (lib "Space Concordia") (part "Resistor"))
    )
    (comp (ref "R29")
      (value "49.9")
      (footprint "R0603B")
      (description "Resistor")
      (libsource (lib "Space Concordia") (part "Resistor"))
    )
    (comp (ref "R30")
      (value "1k")
      (footprint "R0603B")
      (description "Resistor")
      (libsource (lib "Space Concordia") (part "Resistor"))
    )
    (comp (ref "R31")
      (value "100k")
      (footprint "R0603B")
      (description "Resistor")
      (fields (field (name "ALTIUM_VALUE") "100k"))
      (libsource (lib "Space Concordia") (part "Resistor"))
    )
    (comp (ref "R32")
      (value "120")
      (footprint "R0603B")
      (description "Resistor")
      (libsource (lib "Space Concordia") (part "Resistor"))
    )
    (comp (ref "R33")
      (value "0")
      (footprint "R0603B")
      (description "Resistor")
      (libsource (lib "Space Concordia") (part "Resistor"))
    )
    (comp (ref "R34")
      (value "0")
      (footprint "R0603B")
      (description "Resistor")
      (libsource (lib "Space Concordia") (part "Resistor"))
    )
    (comp (ref "R35")
      (value "0")
      (footprint "R0603B")
      (description "Resistor")
      (libsource (lib "Space Concordia") (part "Resistor"))
    )
    (comp (ref "R36")
      (value "0")
      (footprint "R0603B")
      (description "Resistor")
      (libsource (lib "Space Concordia") (part "Resistor"))
    )
    (comp (ref "R37")
      (value "0")
      (footprint "R0603B")
      (description "Resistor")
      (libsource (lib "Space Concordia") (part "Resistor"))
    )
    (comp (ref "R38")
      (value "0")
      (footprint "R0603B")
      (description "Resistor")
      (libsource (lib "Space Concordia") (part "Resistor"))
    )
    (comp (ref "R39")
      (value "100k")
      (footprint "R0603B")
      (description "Resistor")
      (libsource (lib "Space Concordia") (part "Resistor"))
    )
    (comp (ref "R40")
      (value "0")
      (footprint "R0603B")
      (description "Resistor")
      (libsource (lib "Space Concordia") (part "Resistor"))
    )
    (comp (ref "R41")
      (value "100k")
      (footprint "R0603B")
      (description "Resistor")
      (libsource (lib "Space Concordia") (part "Resistor"))
    )
    (comp (ref "R42")
      (value "0")
      (footprint "R0603B")
      (description "Resistor")
      (libsource (lib "Space Concordia") (part "Resistor"))
    )
    (comp (ref "R43")
      (value "TBD")
      (footprint "R0603B")
      (description "Resistor")
      (libsource (lib "Space Concordia") (part "Resistor"))
    )
    (comp (ref "U1")
      (value "MAX96724FGTN/V+")
      (footprint "MAX96724FGTN_V+-Footprint-1")
      (description "Quad Tunneling GMSL2/1 to CSI-2 Deserializer")
      (libsource (lib "Space Concordia") (part "MAX96724FGTN_V+-Symbol-1"))
    )
    (comp (ref "U2")
      (value "LD1117S18TR")
      (footprint "SOT-223_M")
      (description "Fixed Low Drop Positive Voltage Regulator, 1.8V, 4-Pin SOT-223, Tape and Reel")
      (libsource (lib "Altium Content Vault") (part "PM-REG-LD1117-SOT4"))
    )
    (comp (ref "U3")
      (value "LD1117S12TR")
      (footprint "SOT-223_M")
      (description "Fixed Low Drop Positive Voltage Regulator, 1.2V, 4-Pin SOT-223, Tape and Reel")
      (libsource (lib "Altium Content Vault") (part "PM-REG-LD1117-SOT4"))
    )
    (comp (ref "U4")
      (value "PAC1934T-I/JQ")
      (footprint "FP-C04-257-MFG")
      (description "QUAD HIGH-SIDE CURRENT SENSOR")
      (libsource (lib "Altium Content Vault") (part "528e103f3bb2621196c8a4997bef883"))
    )
    (comp (ref "Y1")
      (value "ABM8G-25.000MHZ-18-D2Y-T")
      (footprint "FP-ABM8G-MFG")
      (description "Crystal 25MHz ±20ppm (Tol) ±30ppm (Stability) 18pF FUND 60Ω 4-Pin SMD T/R")
      (fields (field (name "TOLERANCE") "20ppm"))
      (libsource (lib "Altium Content Vault") (part "48e526d86b7f2615d98721063c72f49"))
    )
  )
  (nets
    (net (code "1") (name "/1V8_nPWDN") (class "Default")
      (node (ref "Q4") (pin "2") (pinfunction "S_2") (pintype "passive"))
      (node (ref "R24") (pin "1") (pinfunction "1_1") (pintype "passive"))
    )
    (net (code "2") (name "/3V3_MAX96724_nPWDN") (class "Default")
      (node (ref "Q4") (pin "3") (pinfunction "D_3") (pintype "passive"))
      (node (ref "R25") (pin "1") (pinfunction "1_1") (pintype "passive"))
      (node (ref "U1") (pin "11") (pinfunction "PWDNB_11") (pintype "input"))
    )
    (net (code "3") (name "/3V3_SCL") (class "Default")
      (node (ref "U1") (pin "29") (pinfunction "SCL_29") (pintype "passive"))
    )
    (net (code "4") (name "/3V3_SDA") (class "Default")
      (node (ref "U1") (pin "28") (pinfunction "SDA_28") (pintype "passive"))
    )
    (net (code "5") (name "/3V3_SNS_SCL") (class "Default")
      (node (ref "U4") (pin "4") (pinfunction "SM_CLK_4") (pintype "input"))
    )
    (net (code "6") (name "/3V3_SNS_SDA") (class "Default")
      (node (ref "U4") (pin "5") (pinfunction "SM_DATA_5") (pintype "bidirectional"))
    )
    (net (code "7") (name "/3V3_SNS_nALERT") (class "Default")
      (node (ref "R41") (pin "1") (pinfunction "1_1") (pintype "passive"))
      (node (ref "U4") (pin "1") (pinfunction "SLOW/~{ALERT}_1") (pintype "bidirectional"))
    )
    (net (code "8") (name "/3V3_nERRB") (class "Default")
      (node (ref "U1") (pin "14") (pinfunction "MFP5_14") (pintype "bidirectional"))
    )
    (net (code "9") (name "/3V3_nLOCK") (class "Default")
      (node (ref "U1") (pin "13") (pinfunction "MFP4_13") (pintype "bidirectional"))
    )
    (net (code "10") (name "/CSI0_CK_N") (class "Default")
      (node (ref "U1") (pin "40") (pinfunction "CKAN_40") (pintype "bidirectional"))
    )
    (net (code "11") (name "/CSI0_CK_P") (class "Default")
      (node (ref "U1") (pin "39") (pinfunction "CKAP_39") (pintype "bidirectional"))
    )
    (net (code "12") (name "/CSI0_D0_N") (class "Default")
      (node (ref "U1") (pin "32") (pinfunction "DA0N_32") (pintype "bidirectional"))
    )
    (net (code "13") (name "/CSI0_D0_P") (class "Default")
      (node (ref "U1") (pin "31") (pinfunction "DA0P_31") (pintype "bidirectional"))
    )
    (net (code "14") (name "/CSI0_D1_N") (class "Default")
      (node (ref "U1") (pin "36") (pinfunction "DA1N_36") (pintype "bidirectional"))
    )
    (net (code "15") (name "/CSI0_D1_P") (class "Default")
      (node (ref "U1") (pin "35") (pinfunction "DA1P_35") (pintype "bidirectional"))
    )
    (net (code "16") (name "/CSI0_D2_N") (class "Default")
      (node (ref "U1") (pin "38") (pinfunction "DA2N_38") (pintype "bidirectional"))
    )
    (net (code "17") (name "/CSI0_D2_P") (class "Default")
      (node (ref "U1") (pin "37") (pinfunction "DA2P_37") (pintype "bidirectional"))
    )
    (net (code "18") (name "/CSI0_D3_N") (class "Default")
      (node (ref "U1") (pin "42") (pinfunction "DA3N_42") (pintype "bidirectional"))
    )
    (net (code "19") (name "/CSI0_D3_P") (class "Default")
      (node (ref "U1") (pin "41") (pinfunction "DA3P_41") (pintype "bidirectional"))
    )
    (net (code "20") (name "/HV_EN_RF_A") (class "Default")
      (node (ref "R7") (pin "2") (pinfunction "2_2") (pintype "passive"))
    )
    (net (code "21") (name "/HV_EN_RF_B") (class "Default")
      (node (ref "R16") (pin "2") (pinfunction "2_2") (pintype "passive"))
    )
    (net (code "22") (name "/HV_EN_RF_C") (class "Default")
      (node (ref "R22") (pin "2") (pinfunction "2_2") (pintype "passive"))
    )
    (net (code "23") (name "/HV_EN_RF_D") (class "Default")
      (node (ref "R30") (pin "2") (pinfunction "2_2") (pintype "passive"))
    )
    (net (code "24") (name "/MAX96724_1V2") (class "Default")
      (node (ref "C32") (pin "1") (pinfunction "1_1") (pintype "passive"))
      (node (ref "C44") (pin "2") (pinfunction "2_2") (pintype "passive"))
      (node (ref "C45") (pin "2") (pinfunction "2_2") (pintype "passive"))
      (node (ref "C47") (pin "2") (pinfunction "2_2") (pintype "passive"))
      (node (ref "C48") (pin "2") (pinfunction "2_2") (pintype "passive"))
      (node (ref "C55") (pin "2") (pinfunction "2_2") (pintype "passive"))
      (node (ref "C56") (pin "2") (pinfunction "2_2") (pintype "passive"))
      (node (ref "C57") (pin "1") (pinfunction "1_1") (pintype "passive"))
      (node (ref "R32") (pin "2") (pinfunction "2_2") (pintype "passive"))
      (node (ref "U1") (pin "30") (pinfunction "VTERM_30") (pintype "power_in"))
      (node (ref "U1") (pin "55") (pinfunction "VDD_55") (pintype "power_in"))
      (node (ref "U1") (pin "56") (pinfunction "VDD_56") (pintype "power_in"))
      (node (ref "U3") (pin "2") (pinfunction "VOUT_2") (pintype "power_in"))
      (node (ref "U3") (pin "4") (pinfunction "VOUT_4") (pintype "power_in"))
    )
    (net (code "25") (name "/MAX96724_1V8") (class "Default")
      (node (ref "C30") (pin "1") (pinfunction "1_1") (pintype "passive"))
      (node (ref "C49") (pin "2") (pinfunction "2_2") (pintype "passive"))
      (node (ref "C50") (pin "2") (pinfunction "2_2") (pintype "passive"))
      (node (ref "C51") (pin "2") (pinfunction "2_2") (pintype "passive"))
      (node (ref "C52") (pin "2") (pinfunction "2_2") (pintype "passive"))
      (node (ref "C58") (pin "1") (pinfunction "1_1") (pintype "passive"))
      (node (ref "U1") (pin "21") (pinfunction "VDD18_21") (pintype "power_in"))
      (node (ref "U1") (pin "7") (pinfunction "VDD18_7") (pintype "power_in"))
      (node (ref "U2") (pin "2") (pinfunction "VOUT_2") (pintype "power_in"))
      (node (ref "U2") (pin "4") (pinfunction "VOUT_4") (pintype "power_in"))
    )
    (net (code "26") (name "/MAX96724_3V3") (class "Default")
      (node (ref "C29") (pin "2") (pinfunction "2_2") (pintype "passive"))
      (node (ref "C31") (pin "2") (pinfunction "2_2") (pintype "passive"))
      (node (ref "C53") (pin "2") (pinfunction "2_2") (pintype "passive"))
      (node (ref "C54") (pin "2") (pinfunction "2_2") (pintype "passive"))
      (node (ref "C59") (pin "1") (pinfunction "1_1") (pintype "passive"))
      (node (ref "R10") (pin "2") (pinfunction "2_2") (pintype "passive"))
      (node (ref "R2") (pin "2") (pinfunction "2_2") (pintype "passive"))
      (node (ref "R25") (pin "2") (pinfunction "2_2") (pintype "passive"))
      (node (ref "U1") (pin "24") (pinfunction "VDDIO_24") (pintype "power_in"))
      (node (ref "U2") (pin "3") (pinfunction "VIN_3") (pintype "power_in"))
      (node (ref "U3") (pin "3") (pinfunction "VIN_3") (pintype "power_in"))
    )
    (net (code "27") (name "/MAX96724_CFG0") (class "Default")
      (node (ref "R2") (pin "1") (pinfunction "1_1") (pintype "passive"))
      (node (ref "R5") (pin "2") (pinfunction "2_2") (pintype "passive"))
      (node (ref "U1") (pin "4") (pinfunction "CFG0_4") (pintype "input"))
    )
    (net (code "28") (name "/MAX96724_CFG1") (class "Default")
      (node (ref "R10") (pin "1") (pinfunction "1_1") (pintype "passive"))
      (node (ref "R14") (pin "2") (pinfunction "2_2") (pintype "passive"))
      (node (ref "U1") (pin "25") (pinfunction "CFG1/MFP6_25") (pintype "bidirectional"))
    )
    (net (code "29") (name "/MAX96724_PoC_A") (class "Default")
      (node (ref "C1") (pin "2") (pinfunction "2_2") (pintype "passive"))
      (node (ref "L3") (pin "2") (pinfunction "2_2") (pintype "passive"))
    )
    (net (code "30") (name "/MAX96724_PoC_A_V_N") (class "Default")
      (node (ref "L1") (pin "1") (pinfunction "1_1") (pintype "passive"))
      (node (ref "R1") (pin "1") (pinfunction "1_1") (pintype "passive"))
      (node (ref "R34") (pin "1") (pinfunction "1_1") (pintype "passive"))
    )
    (net (code "31") (name "/MAX96724_PoC_A_V_P") (class "Default")
      (node (ref "C4") (pin "2") (pinfunction "2_2") (pintype "passive"))
      (node (ref "Q1") (pin "4") (pinfunction "D_4") (pintype "passive"))
      (node (ref "R1") (pin "2") (pinfunction "2_2") (pintype "passive"))
      (node (ref "R33") (pin "1") (pinfunction "1_1") (pintype "passive"))
    )
    (net (code "32") (name "/MAX96724_PoC_B") (class "Default")
      (node (ref "C9") (pin "2") (pinfunction "2_2") (pintype "passive"))
      (node (ref "L6") (pin "2") (pinfunction "2_2") (pintype "passive"))
    )
    (net (code "33") (name "/MAX96724_PoC_B_V_N") (class "Default")
      (node (ref "L4") (pin "1") (pinfunction "1_1") (pintype "passive"))
      (node (ref "R36") (pin "1") (pinfunction "1_1") (pintype "passive"))
      (node (ref "R9") (pin "1") (pinfunction "1_1") (pintype "passive"))
    )
    (net (code "34") (name "/MAX96724_PoC_B_V_P") (class "Default")
      (node (ref "C16") (pin "2") (pinfunction "2_2") (pintype "passive"))
      (node (ref "Q2") (pin "4") (pinfunction "D_4") (pintype "passive"))
      (node (ref "R35") (pin "1") (pinfunction "1_1") (pintype "passive"))
      (node (ref "R9") (pin "2") (pinfunction "2_2") (pintype "passive"))
    )
    (net (code "35") (name "/MAX96724_PoC_C") (class "Default")
      (node (ref "C19") (pin "2") (pinfunction "2_2") (pintype "passive"))
      (node (ref "L9") (pin "2") (pinfunction "2_2") (pintype "passive"))
    )
    (net (code "36") (name "/MAX96724_PoC_C_V_N") (class "Default")
      (node (ref "L7") (pin "1") (pinfunction "1_1") (pintype "passive"))
      (node (ref "R18") (pin "1") (pinfunction "1_1") (pintype "passive"))
      (node (ref "R38") (pin "1") (pinfunction "1_1") (pintype "passive"))
    )
    (net (code "37") (name "/MAX96724_PoC_C_V_P") (class "Default")
      (node (ref "C24") (pin "2") (pinfunction "2_2") (pintype "passive"))
      (node (ref "Q3") (pin "4") (pinfunction "D_4") (pintype "passive"))
      (node (ref "R18") (pin "2") (pinfunction "2_2") (pintype "passive"))
      (node (ref "R37") (pin "1") (pinfunction "1_1") (pintype "passive"))
    )
    (net (code "38") (name "/MAX96724_PoC_D") (class "Default")
      (node (ref "C25") (pin "2") (pinfunction "2_2") (pintype "passive"))
      (node (ref "L12") (pin "2") (pinfunction "2_2") (pintype "passive"))
    )
    (net (code "39") (name "/MAX96724_PoC_D_V_N") (class "Default")
      (node (ref "L10") (pin "1") (pinfunction "1_1") (pintype "passive"))
      (node (ref "R26") (pin "1") (pinfunction "1_1") (pintype "passive"))
      (node (ref "R42") (pin "1") (pinfunction "1_1") (pintype "passive"))
    )
    (net (code "40") (name "/MAX96724_PoC_D_V_P") (class "Default")
      (node (ref "C28") (pin "2") (pinfunction "2_2") (pintype "passive"))
      (node (ref "Q5") (pin "4") (pinfunction "D_4") (pintype "passive"))
      (node (ref "R26") (pin "2") (pinfunction "2_2") (pintype "passive"))
      (node (ref "R40") (pin "1") (pinfunction "1_1") (pintype "passive"))
    )
    (net (code "41") (name "/MAX96724_SIOA_N") (class "Default")
      (node (ref "C3") (pin "1") (pinfunction "1_1") (pintype "passive"))
      (node (ref "U1") (pin "22") (pinfunction "SIOAN_22") (pintype "bidirectional"))
    )
    (net (code "42") (name "/MAX96724_SIOA_P") (class "Default")
      (node (ref "C1") (pin "1") (pinfunction "1_1") (pintype "passive"))
      (node (ref "U1") (pin "23") (pinfunction "SIOAP_23") (pintype "bidirectional"))
    )
    (net (code "43") (name "/MAX96724_SIOB_N") (class "Default")
      (node (ref "C15") (pin "1") (pinfunction "1_1") (pintype "passive"))
      (node (ref "U1") (pin "19") (pinfunction "SIOBN_19") (pintype "bidirectional"))
    )
    (net (code "44") (name "/MAX96724_SIOB_P") (class "Default")
      (node (ref "C9") (pin "1") (pinfunction "1_1") (pintype "passive"))
      (node (ref "U1") (pin "18") (pinfunction "SIOBP_18") (pintype "bidirectional"))
    )
    (net (code "45") (name "/MAX96724_SIOC_N") (class "Default")
      (node (ref "C23") (pin "1") (pinfunction "1_1") (pintype "passive"))
      (node (ref "U1") (pin "9") (pinfunction "SIOCN_9") (pintype "bidirectional"))
    )
    (net (code "46") (name "/MAX96724_SIOC_P") (class "Default")
      (node (ref "C19") (pin "1") (pinfunction "1_1") (pintype "passive"))
      (node (ref "U1") (pin "10") (pinfunction "SIOCP_10") (pintype "bidirectional"))
    )
    (net (code "47") (name "/MAX96724_SIOD_N") (class "Default")
      (node (ref "C27") (pin "1") (pinfunction "1_1") (pintype "passive"))
      (node (ref "U1") (pin "6") (pinfunction "SIODN_6") (pintype "bidirectional"))
    )
    (net (code "48") (name "/MAX96724_SIOD_P") (class "Default")
      (node (ref "C25") (pin "1") (pinfunction "1_1") (pintype "passive"))
      (node (ref "U1") (pin "5") (pinfunction "SIODP_5") (pintype "bidirectional"))
    )
    (net (code "49") (name "/MAX96724_X_N") (class "Default")
      (node (ref "C21") (pin "2") (pinfunction "2_2") (pintype "passive"))
      (node (ref "U1") (pin "16") (pinfunction "X2_16") (pintype "passive"))
      (node (ref "Y1") (pin "3") (pinfunction "3_3") (pintype "passive"))
    )
    (net (code "50") (name "/MAX96724_X_P") (class "Default")
      (node (ref "C20") (pin "2") (pinfunction "2_2") (pintype "passive"))
      (node (ref "U1") (pin "15") (pinfunction "X1/OSC_15") (pintype "passive"))
      (node (ref "Y1") (pin "1") (pinfunction "1_1") (pintype "passive"))
    )
    (net (code "51") (name "/PoC_PWR") (class "Default")
      (node (ref "F1") (pin "1") (pinfunction "1_1") (pintype "passive"))
      (node (ref "F2") (pin "1") (pinfunction "1_1") (pintype "passive"))
      (node (ref "F3") (pin "1") (pinfunction "1_1") (pintype "passive"))
      (node (ref "F4") (pin "1") (pinfunction "1_1") (pintype "passive"))
    )
    (net (code "52") (name "3V3_INT") (class "Default")
      (node (ref "C36") (pin "2") (pinfunction "2_2") (pintype "passive"))
      (node (ref "C37") (pin "2") (pinfunction "2_2") (pintype "passive"))
      (node (ref "R39") (pin "2") (pinfunction "2_2") (pintype "passive"))
      (node (ref "R41") (pin "2") (pinfunction "2_2") (pintype "passive"))
      (node (ref "U4") (pin "15") (pinfunction "VDD_I/O_15") (pintype "power_in"))
      (node (ref "U4") (pin "2") (pinfunction "VDD_2") (pintype "power_in"))
    )
    (net (code "53") (name "GND") (class "Default")
      (node (ref "C14") (pin "2") (pinfunction "2_2") (pintype "passive"))
      (node (ref "C16") (pin "1") (pinfunction "1_1") (pintype "passive"))
      (node (ref "C2") (pin "2") (pinfunction "2_2") (pintype "passive"))
      (node (ref "C20") (pin "1") (pinfunction "1_1") (pintype "passive"))
      (node (ref "C21") (pin "1") (pinfunction "1_1") (pintype "passive"))
      (node (ref "C22") (pin "2") (pinfunction "2_2") (pintype "passive"))
      (node (ref "C24") (pin "1") (pinfunction "1_1") (pintype "passive"))
      (node (ref "C26") (pin "2") (pinfunction "2_2") (pintype "passive"))
      (node (ref "C28") (pin "1") (pinfunction "1_1") (pintype "passive"))
      (node (ref "C29") (pin "1") (pinfunction "1_1") (pintype "passive"))
      (node (ref "C30") (pin "2") (pinfunction "2_2") (pintype "passive"))
      (node (ref "C31") (pin "1") (pinfunction "1_1") (pintype "passive"))
      (node (ref "C32") (pin "2") (pinfunction "2_2") (pintype "passive"))
      (node (ref "C36") (pin "1") (pinfunction "1_1") (pintype "passive"))
      (node (ref "C37") (pin "1") (pinfunction "1_1") (pintype "passive"))
      (node (ref "C38") (pin "1") (pinfunction "1_1") (pintype "passive"))
      (node (ref "C39") (pin "1") (pinfunction "1_1") (pintype "passive"))
      (node (ref "C4") (pin "1") (pinfunction "1_1") (pintype "passive"))
      (node (ref "C40") (pin "1") (pinfunction "1_1") (pintype "passive"))
      (node (ref "C41") (pin "1") (pinfunction "1_1") (pintype "passive"))
      (node (ref "C42") (pin "1") (pinfunction "1_1") (pintype "passive"))
      (node (ref "C43") (pin "1") (pinfunction "1_1") (pintype "passive"))
      (node (ref "C44") (pin "1") (pinfunction "1_1") (pintype "passive"))
      (node (ref "C45") (pin "1") (pinfunction "1_1") (pintype "passive"))
      (node (ref "C47") (pin "1") (pinfunction "1_1") (pintype "passive"))
      (node (ref "C48") (pin "1") (pinfunction "1_1") (pintype "passive"))
      (node (ref "C49") (pin "1") (pinfunction "1_1") (pintype "passive"))
      (node (ref "C50") (pin "1") (pinfunction "1_1") (pintype "passive"))
      (node (ref "C51") (pin "1") (pinfunction "1_1") (pintype "passive"))
      (node (ref "C52") (pin "1") (pinfunction "1_1") (pintype "passive"))
      (node (ref "C53") (pin "1") (pinfunction "1_1") (pintype "passive"))
      (node (ref "C54") (pin "1") (pinfunction "1_1") (pintype "passive"))
      (node (ref "C55") (pin "1") (pinfunction "1_1") (pintype "passive"))
      (node (ref "C56") (pin "1") (pinfunction "1_1") (pintype "passive"))
      (node (ref "C57") (pin "2") (pinfunction "2_2") (pintype "passive"))
      (node (ref "C58") (pin "2") (pinfunction "2_2") (pintype "passive"))
      (node (ref "C59") (pin "2") (pinfunction "2_2") (pintype "passive"))
      (node (ref "Q1") (pin "5") (pinfunction "S_5") (pintype "passive"))
      (node (ref "Q2") (pin "5") (pinfunction "S_5") (pintype "passive"))
      (node (ref "Q3") (pin "5") (pinfunction "S_5") (pintype "passive"))
      (node (ref "Q5") (pin "5") (pinfunction "S_5") (pintype "passive"))
      (node (ref "R13") (pin "1") (pinfunction "1_1") (pintype "passive"))
      (node (ref "R14") (pin "1") (pinfunction "1_1") (pintype "passive"))
      (node (ref "R15") (pin "1") (pinfunction "1_1") (pintype "passive"))
      (node (ref "R17") (pin "1") (pinfunction "1_1") (pintype "passive"))
      (node (ref "R21") (pin "1") (pinfunction "1_1") (pintype "passive"))
      (node (ref "R23") (pin "1") (pinfunction "1_1") (pintype "passive"))
      (node (ref "R29") (pin "1") (pinfunction "1_1") (pintype "passive"))
      (node (ref "R31") (pin "1") (pinfunction "1_1") (pintype "passive"))
      (node (ref "R32") (pin "1") (pinfunction "1_1") (pintype "passive"))
      (node (ref "R43") (pin "2") (pinfunction "2_2") (pintype "passive"))
      (node (ref "R5") (pin "1") (pinfunction "1_1") (pintype "passive"))
      (node (ref "R6") (pin "1") (pinfunction "1_1") (pintype "passive"))
      (node (ref "R8") (pin "1") (pinfunction "1_1") (pintype "passive"))
      (node (ref "U1") (pin "57") (pinfunction "GND_(EP)_57") (pintype "power_in"))
      (node (ref "U2") (pin "1") (pinfunction "GND_1") (pintype "power_in"))
      (node (ref "U3") (pin "1") (pinfunction "GND_1") (pintype "power_in"))
      (node (ref "U4") (pin "17") (pinfunction "Exposed_pad_17") (pintype "passive"))
      (node (ref "U4") (pin "3") (pinfunction "GND_3") (pintype "power_in"))
      (node (ref "Y1") (pin "2") (pinfunction "GND_2") (pintype "power_in"))
      (node (ref "Y1") (pin "4") (pinfunction "GND_4") (pintype "power_in"))
    )
    (net (code "54") (name "JSN_1V8_REF") (class "Default")
      (node (ref "Q4") (pin "1") (pinfunction "G_1") (pintype "passive"))
      (node (ref "R24") (pin "2") (pinfunction "2_2") (pintype "passive"))
    )
    (net (code "55") (name "Net-(C2-Pad1)") (class "Default")
      (node (ref "C2") (pin "1") (pinfunction "1_1") (pintype "passive"))
      (node (ref "L1") (pin "2") (pinfunction "2_2") (pintype "passive"))
      (node (ref "L2") (pin "1") (pinfunction "1_1") (pintype "passive"))
      (node (ref "R4") (pin "2") (pinfunction "2_2") (pintype "passive"))
    )
    (net (code "56") (name "Net-(C3-Pad2)") (class "Default")
      (node (ref "C3") (pin "2") (pinfunction "2_2") (pintype "passive"))
      (node (ref "R6") (pin "2") (pinfunction "2_2") (pintype "passive"))
    )
    (net (code "57") (name "Net-(C14-Pad1)") (class "Default")
      (node (ref "C14") (pin "1") (pinfunction "1_1") (pintype "passive"))
      (node (ref "L4") (pin "2") (pinfunction "2_2") (pintype "passive"))
      (node (ref "L5") (pin "1") (pinfunction "1_1") (pintype "passive"))
      (node (ref "R12") (pin "2") (pinfunction "2_2") (pintype "passive"))
    )
    (net (code "58") (name "Net-(C15-Pad2)") (class "Default")
      (node (ref "C15") (pin "2") (pinfunction "2_2") (pintype "passive"))
      (node (ref "R15") (pin "2") (pinfunction "2_2") (pintype "passive"))
    )
    (net (code "59") (name "Net-(C22-Pad1)") (class "Default")
      (node (ref "C22") (pin "1") (pinfunction "1_1") (pintype "passive"))
      (node (ref "L7") (pin "2") (pinfunction "2_2") (pintype "passive"))
      (node (ref "L8") (pin "1") (pinfunction "1_1") (pintype "passive"))
      (node (ref "R20") (pin "2") (pinfunction "2_2") (pintype "passive"))
    )
    (net (code "60") (name "Net-(C23-Pad2)") (class "Default")
      (node (ref "C23") (pin "2") (pinfunction "2_2") (pintype "passive"))
      (node (ref "R21") (pin "2") (pinfunction "2_2") (pintype "passive"))
    )
    (net (code "61") (name "Net-(C26-Pad1)") (class "Default")
      (node (ref "C26") (pin "1") (pinfunction "1_1") (pintype "passive"))
      (node (ref "L10") (pin "2") (pinfunction "2_2") (pintype "passive"))
      (node (ref "L11") (pin "1") (pinfunction "1_1") (pintype "passive"))
      (node (ref "R28") (pin "2") (pinfunction "2_2") (pintype "passive"))
    )
    (net (code "62") (name "Net-(C27-Pad2)") (class "Default")
      (node (ref "C27") (pin "2") (pinfunction "2_2") (pintype "passive"))
      (node (ref "R29") (pin "2") (pinfunction "2_2") (pintype "passive"))
    )
    (net (code "63") (name "Net-(C38-Pad2)") (class "Default")
      (node (ref "C38") (pin "2") (pinfunction "2_2") (pintype "passive"))
      (node (ref "C39") (pin "2") (pinfunction "2_2") (pintype "passive"))
      (node (ref "C40") (pin "2") (pinfunction "2_2") (pintype "passive"))
      (node (ref "U1") (pin "8") (pinfunction "CAP_VDD_8") (pintype "power_in"))
    )
    (net (code "64") (name "Net-(C41-Pad2)") (class "Default")
      (node (ref "C41") (pin "2") (pinfunction "2_2") (pintype "passive"))
      (node (ref "C42") (pin "2") (pinfunction "2_2") (pintype "passive"))
      (node (ref "C43") (pin "2") (pinfunction "2_2") (pintype "passive"))
      (node (ref "U1") (pin "20") (pinfunction "CAP_VDD_20") (pintype "power_in"))
    )
    (net (code "65") (name "Net-(L2-Pad2)") (class "Default")
      (node (ref "L2") (pin "2") (pinfunction "2_2") (pintype "passive"))
      (node (ref "L3") (pin "1") (pinfunction "1_1") (pintype "passive"))
      (node (ref "R4") (pin "1") (pinfunction "1_1") (pintype "passive"))
    )
    (net (code "66") (name "Net-(L5-Pad2)") (class "Default")
      (node (ref "L5") (pin "2") (pinfunction "2_2") (pintype "passive"))
      (node (ref "L6") (pin "1") (pinfunction "1_1") (pintype "passive"))
      (node (ref "R12") (pin "1") (pinfunction "1_1") (pintype "passive"))
    )
    (net (code "67") (name "Net-(L8-Pad2)") (class "Default")
      (node (ref "L8") (pin "2") (pinfunction "2_2") (pintype "passive"))
      (node (ref "L9") (pin "1") (pinfunction "1_1") (pintype "passive"))
      (node (ref "R20") (pin "1") (pinfunction "1_1") (pintype "passive"))
    )
    (net (code "68") (name "Net-(L11-Pad2)") (class "Default")
      (node (ref "L11") (pin "2") (pinfunction "2_2") (pintype "passive"))
      (node (ref "L12") (pin "1") (pinfunction "1_1") (pintype "passive"))
      (node (ref "R28") (pin "1") (pinfunction "1_1") (pintype "passive"))
    )
    (net (code "69") (name "Net-(Q1A-G)") (class "Default")
      (node (ref "Q1") (pin "3") (pinfunction "G_3") (pintype "passive"))
      (node (ref "Q1") (pin "6") (pinfunction "D_6") (pintype "passive"))
      (node (ref "R3") (pin "1") (pinfunction "1_1") (pintype "passive"))
    )
    (net (code "70") (name "Net-(Q1A-S)") (class "Default")
      (node (ref "F1") (pin "2") (pinfunction "2_2") (pintype "passive"))
      (node (ref "Q1") (pin "2") (pinfunction "S_2") (pintype "passive"))
      (node (ref "R3") (pin "2") (pinfunction "2_2") (pintype "passive"))
    )
    (net (code "71") (name "Net-(Q1B-G)") (class "Default")
      (node (ref "Q1") (pin "1") (pinfunction "G_1") (pintype "passive"))
      (node (ref "R7") (pin "1") (pinfunction "1_1") (pintype "passive"))
      (node (ref "R8") (pin "2") (pinfunction "2_2") (pintype "passive"))
    )
    (net (code "72") (name "Net-(Q2A-G)") (class "Default")
      (node (ref "Q2") (pin "3") (pinfunction "G_3") (pintype "passive"))
      (node (ref "Q2") (pin "6") (pinfunction "D_6") (pintype "passive"))
      (node (ref "R11") (pin "1") (pinfunction "1_1") (pintype "passive"))
    )
    (net (code "73") (name "Net-(Q2A-S)") (class "Default")
      (node (ref "F2") (pin "2") (pinfunction "2_2") (pintype "passive"))
      (node (ref "Q2") (pin "2") (pinfunction "S_2") (pintype "passive"))
      (node (ref "R11") (pin "2") (pinfunction "2_2") (pintype "passive"))
    )
    (net (code "74") (name "Net-(Q2B-G)") (class "Default")
      (node (ref "Q2") (pin "1") (pinfunction "G_1") (pintype "passive"))
      (node (ref "R16") (pin "1") (pinfunction "1_1") (pintype "passive"))
      (node (ref "R17") (pin "2") (pinfunction "2_2") (pintype "passive"))
    )
    (net (code "75") (name "Net-(Q3A-G)") (class "Default")
      (node (ref "Q3") (pin "3") (pinfunction "G_3") (pintype "passive"))
      (node (ref "Q3") (pin "6") (pinfunction "D_6") (pintype "passive"))
      (node (ref "R19") (pin "1") (pinfunction "1_1") (pintype "passive"))
    )
    (net (code "76") (name "Net-(Q3A-S)") (class "Default")
      (node (ref "F3") (pin "2") (pinfunction "2_2") (pintype "passive"))
      (node (ref "Q3") (pin "2") (pinfunction "S_2") (pintype "passive"))
      (node (ref "R19") (pin "2") (pinfunction "2_2") (pintype "passive"))
    )
    (net (code "77") (name "Net-(Q3B-G)") (class "Default")
      (node (ref "Q3") (pin "1") (pinfunction "G_1") (pintype "passive"))
      (node (ref "R22") (pin "1") (pinfunction "1_1") (pintype "passive"))
      (node (ref "R23") (pin "2") (pinfunction "2_2") (pintype "passive"))
    )
    (net (code "78") (name "Net-(Q5A-G)") (class "Default")
      (node (ref "Q5") (pin "3") (pinfunction "G_3") (pintype "passive"))
      (node (ref "Q5") (pin "6") (pinfunction "D_6") (pintype "passive"))
      (node (ref "R27") (pin "1") (pinfunction "1_1") (pintype "passive"))
    )
    (net (code "79") (name "Net-(Q5A-S)") (class "Default")
      (node (ref "F4") (pin "2") (pinfunction "2_2") (pintype "passive"))
      (node (ref "Q5") (pin "2") (pinfunction "S_2") (pintype "passive"))
      (node (ref "R27") (pin "2") (pinfunction "2_2") (pintype "passive"))
    )
    (net (code "80") (name "Net-(Q5B-G)") (class "Default")
      (node (ref "Q5") (pin "1") (pinfunction "G_1") (pintype "passive"))
      (node (ref "R30") (pin "1") (pinfunction "1_1") (pintype "passive"))
      (node (ref "R31") (pin "2") (pinfunction "2_2") (pintype "passive"))
    )
    (net (code "81") (name "Net-(U1A-XRES)") (class "Default")
      (node (ref "R13") (pin "2") (pinfunction "2_2") (pintype "passive"))
      (node (ref "U1") (pin "17") (pinfunction "XRES_17") (pintype "passive"))
    )
    (net (code "82") (name "Net-(U4-ADDRSEL)") (class "Default")
      (node (ref "R43") (pin "1") (pinfunction "1_1") (pintype "passive"))
      (node (ref "U4") (pin "6") (pinfunction "ADDRSEL_6") (pintype "input"))
    )
    (net (code "83") (name "Net-(U4-SENSE1+)") (class "Default")
      (node (ref "C33") (pin "2") (pinfunction "2_2") (pintype "passive"))
      (node (ref "R33") (pin "2") (pinfunction "2_2") (pintype "passive"))
      (node (ref "U4") (pin "11") (pinfunction "SENSE1+_11") (pintype "passive"))
    )
    (net (code "84") (name "Net-(U4-SENSE1-)") (class "Default")
      (node (ref "C33") (pin "1") (pinfunction "1_1") (pintype "passive"))
      (node (ref "R34") (pin "2") (pinfunction "2_2") (pintype "passive"))
      (node (ref "U4") (pin "12") (pinfunction "SENSE1-_12") (pintype "passive"))
    )
    (net (code "85") (name "Net-(U4-SENSE2+)") (class "Default")
      (node (ref "C34") (pin "2") (pinfunction "2_2") (pintype "passive"))
      (node (ref "R35") (pin "2") (pinfunction "2_2") (pintype "passive"))
      (node (ref "U4") (pin "13") (pinfunction "SENSE2+_13") (pintype "passive"))
    )
    (net (code "86") (name "Net-(U4-SENSE2-)") (class "Default")
      (node (ref "C34") (pin "1") (pinfunction "1_1") (pintype "passive"))
      (node (ref "R36") (pin "2") (pinfunction "2_2") (pintype "passive"))
      (node (ref "U4") (pin "14") (pinfunction "SENSE2-_14") (pintype "passive"))
    )
    (net (code "87") (name "Net-(U4-SENSE3+)") (class "Default")
      (node (ref "C35") (pin "2") (pinfunction "2_2") (pintype "passive"))
      (node (ref "R37") (pin "2") (pinfunction "2_2") (pintype "passive"))
      (node (ref "U4") (pin "8") (pinfunction "SENSE3+_8") (pintype "passive"))
    )
    (net (code "88") (name "Net-(U4-SENSE3-)") (class "Default")
      (node (ref "C35") (pin "1") (pinfunction "1_1") (pintype "passive"))
      (node (ref "R38") (pin "2") (pinfunction "2_2") (pintype "passive"))
      (node (ref "U4") (pin "7") (pinfunction "SENSE3-_7") (pintype "passive"))
    )
    (net (code "89") (name "Net-(U4-SENSE4+)") (class "Default")
      (node (ref "C46") (pin "2") (pinfunction "2_2") (pintype "passive"))
      (node (ref "R40") (pin "2") (pinfunction "2_2") (pintype "passive"))
      (node (ref "U4") (pin "10") (pinfunction "SENSE4+_10") (pintype "passive"))
    )
    (net (code "90") (name "Net-(U4-SENSE4-)") (class "Default")
      (node (ref "C46") (pin "1") (pinfunction "1_1") (pintype "passive"))
      (node (ref "R42") (pin "2") (pinfunction "2_2") (pintype "passive"))
      (node (ref "U4") (pin "9") (pinfunction "SENSE4-_9") (pintype "passive"))
    )
    (net (code "91") (name "Net-(U4-~{PWRDN})") (class "Default")
      (node (ref "R39") (pin "1") (pinfunction "1_1") (pintype "passive"))
      (node (ref "U4") (pin "16") (pinfunction "~{PWRDN}_16") (pintype "input"))
    )
    (net (code "92") (name "unconnected-(U1A-CKCN-Pad34)") (class "Default")
      (node (ref "U1") (pin "34") (pinfunction "CKCN_34") (pintype "bidirectional+no_connect"))
    )
    (net (code "93") (name "unconnected-(U1A-CKCP-Pad33)") (class "Default")
      (node (ref "U1") (pin "33") (pinfunction "CKCP_33") (pintype "bidirectional+no_connect"))
    )
    (net (code "94") (name "unconnected-(U1B-MFP0-Pad1)") (class "Default")
      (node (ref "U1") (pin "1") (pinfunction "MFP0_1") (pintype "bidirectional+no_connect"))
    )
    (net (code "95") (name "unconnected-(U1B-MFP1-Pad2)") (class "Default")
      (node (ref "U1") (pin "2") (pinfunction "MFP1_2") (pintype "bidirectional+no_connect"))
    )
    (net (code "96") (name "unconnected-(U1B-MFP2-Pad3)") (class "Default")
      (node (ref "U1") (pin "3") (pinfunction "MFP2_3") (pintype "bidirectional+no_connect"))
    )
    (net (code "97") (name "unconnected-(U1B-MFP3-Pad12)") (class "Default")
      (node (ref "U1") (pin "12") (pinfunction "MFP3_12") (pintype "bidirectional+no_connect"))
    )
    (net (code "98") (name "unconnected-(U1B-NC{slash}CKBN-Pad46)") (class "Default")
      (node (ref "U1") (pin "46") (pinfunction "NC/CKBN_46") (pintype "passive+no_connect"))
    )
    (net (code "99") (name "unconnected-(U1B-NC{slash}CKBP-Pad45)") (class "Default")
      (node (ref "U1") (pin "45") (pinfunction "NC/CKBP_45") (pintype "passive+no_connect"))
    )
    (net (code "100") (name "unconnected-(U1B-NC{slash}CKFN-Pad52)") (class "Default")
      (node (ref "U1") (pin "52") (pinfunction "NC/CKFN_52") (pintype "passive+no_connect"))
    )
    (net (code "101") (name "unconnected-(U1B-NC{slash}CKFP-Pad51)") (class "Default")
      (node (ref "U1") (pin "51") (pinfunction "NC/CKFP_51") (pintype "passive+no_connect"))
    )
    (net (code "102") (name "unconnected-(U1B-NC{slash}DB0N-Pad44)") (class "Default")
      (node (ref "U1") (pin "44") (pinfunction "NC/DB0N_44") (pintype "passive+no_connect"))
    )
    (net (code "103") (name "unconnected-(U1B-NC{slash}DB0P-Pad43)") (class "Default")
      (node (ref "U1") (pin "43") (pinfunction "NC/DB0P_43") (pintype "passive+no_connect"))
    )
    (net (code "104") (name "unconnected-(U1B-NC{slash}DB1N-Pad48)") (class "Default")
      (node (ref "U1") (pin "48") (pinfunction "NC/DB1N_48") (pintype "passive+no_connect"))
    )
    (net (code "105") (name "unconnected-(U1B-NC{slash}DB1P-Pad47)") (class "Default")
      (node (ref "U1") (pin "47") (pinfunction "NC/DB1P_47") (pintype "passive+no_connect"))
    )
    (net (code "106") (name "unconnected-(U1B-NC{slash}DB2N-Pad50)") (class "Default")
      (node (ref "U1") (pin "50") (pinfunction "NC/DB2N_50") (pintype "passive+no_connect"))
    )
    (net (code "107") (name "unconnected-(U1B-NC{slash}DB2P-Pad49)") (class "Default")
      (node (ref "U1") (pin "49") (pinfunction "NC/DB2P_49") (pintype "passive+no_connect"))
    )
    (net (code "108") (name "unconnected-(U1B-NC{slash}DB3N-Pad54)") (class "Default")
      (node (ref "U1") (pin "54") (pinfunction "NC/DB3N_54") (pintype "passive+no_connect"))
    )
    (net (code "109") (name "unconnected-(U1B-NC{slash}DB3P-Pad53)") (class "Default")
      (node (ref "U1") (pin "53") (pinfunction "NC/DB3P_53") (pintype "passive+no_connect"))
    )
    (net (code "110") (name "unconnected-(U1B-SCL1{slash}MFP8-Pad27)") (class "Default")
      (node (ref "U1") (pin "27") (pinfunction "SCL1/MFP8_27") (pintype "bidirectional+no_connect"))
    )
    (net (code "111") (name "unconnected-(U1B-SDA1{slash}MFP7-Pad26)") (class "Default")
      (node (ref "U1") (pin "26") (pinfunction "SDA1/MFP7_26") (pintype "bidirectional+no_connect"))
    )
  )
)
